# Sheet1.net
KiCad netlist of a schematic drawn in Altium Designer
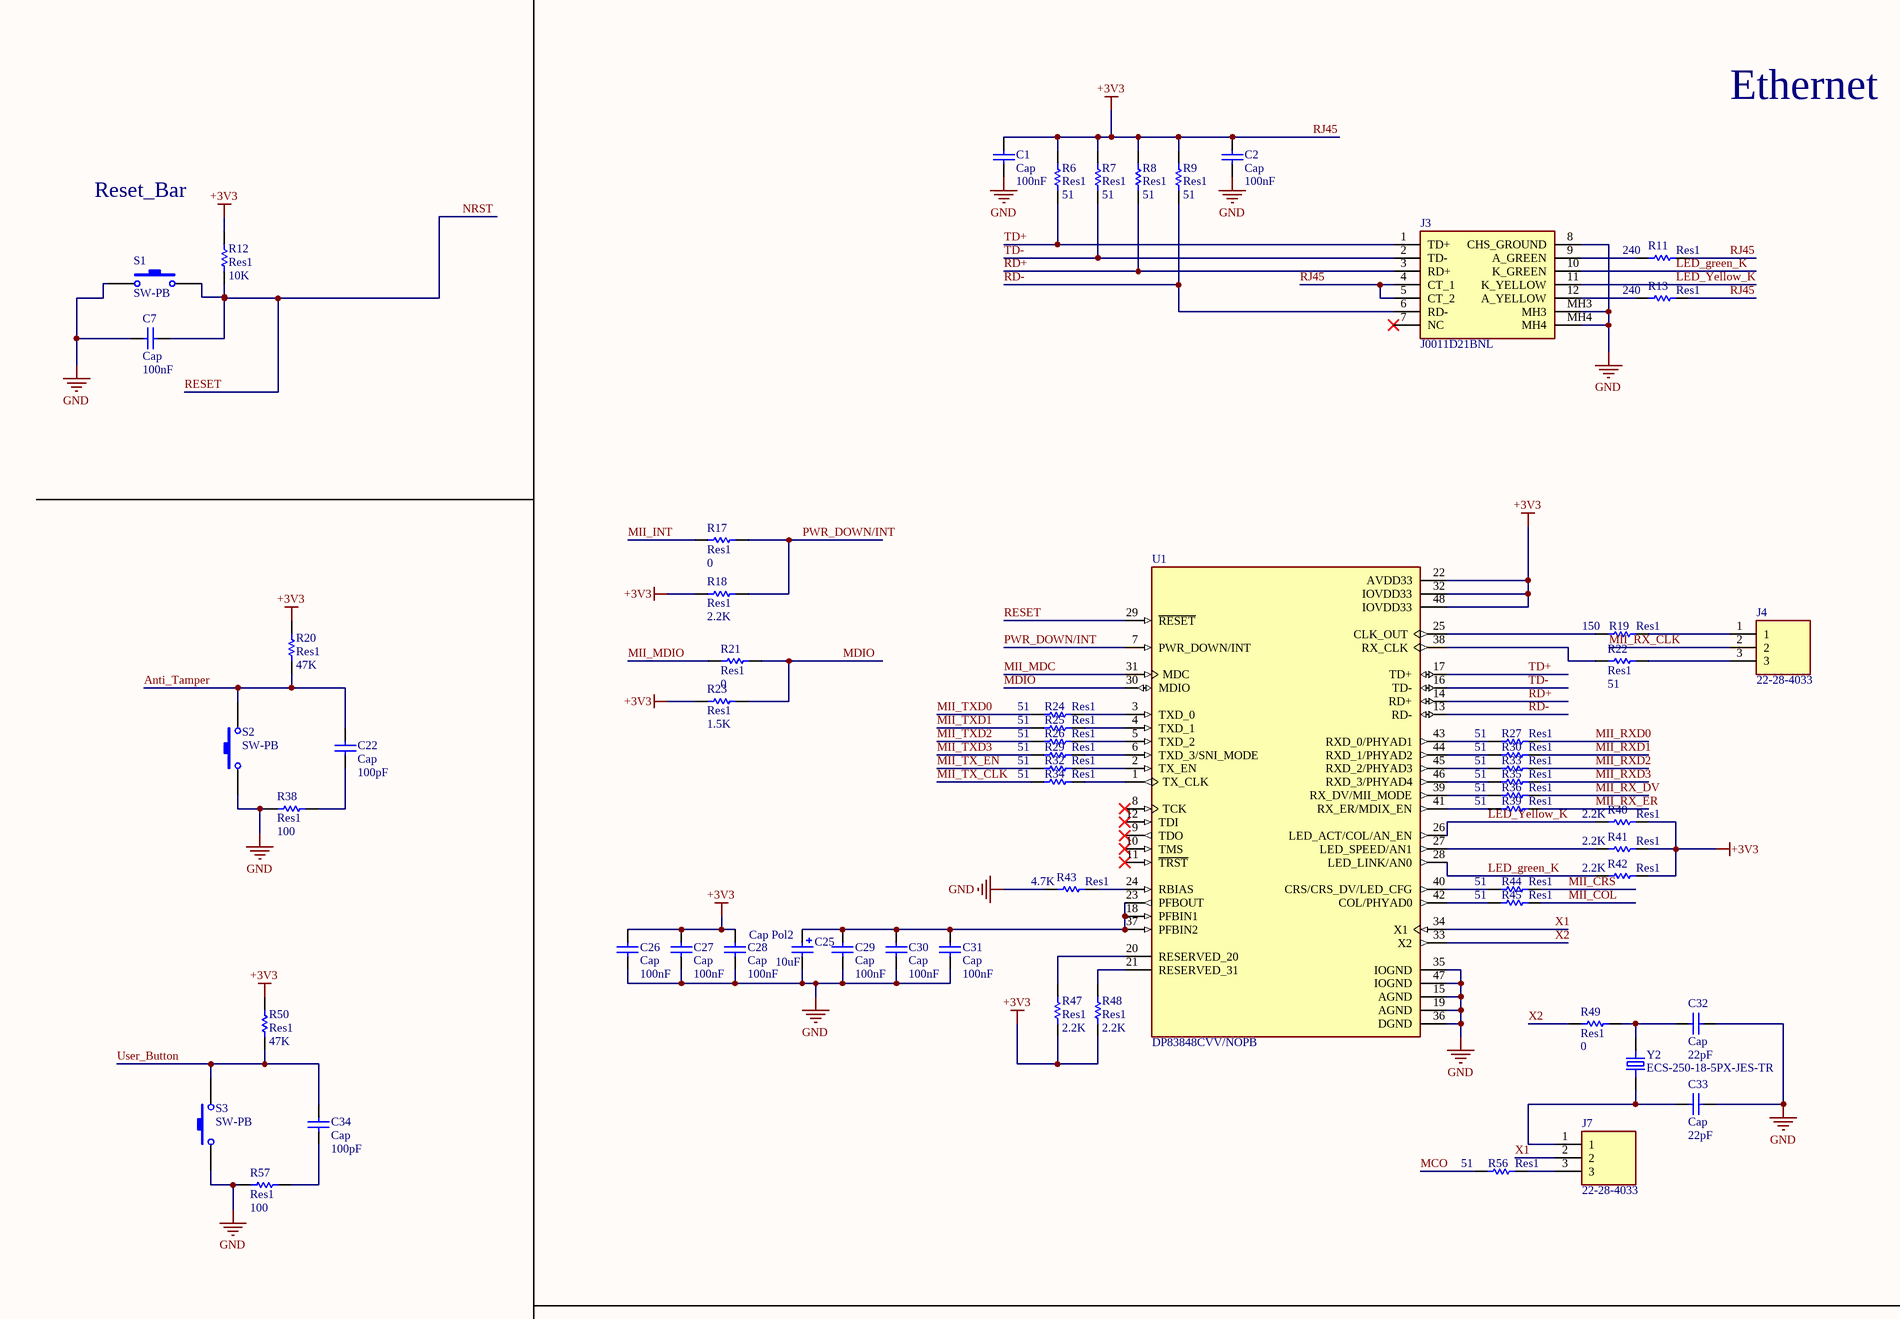
[diagram p0: Sheet1.SchDoc, top left]
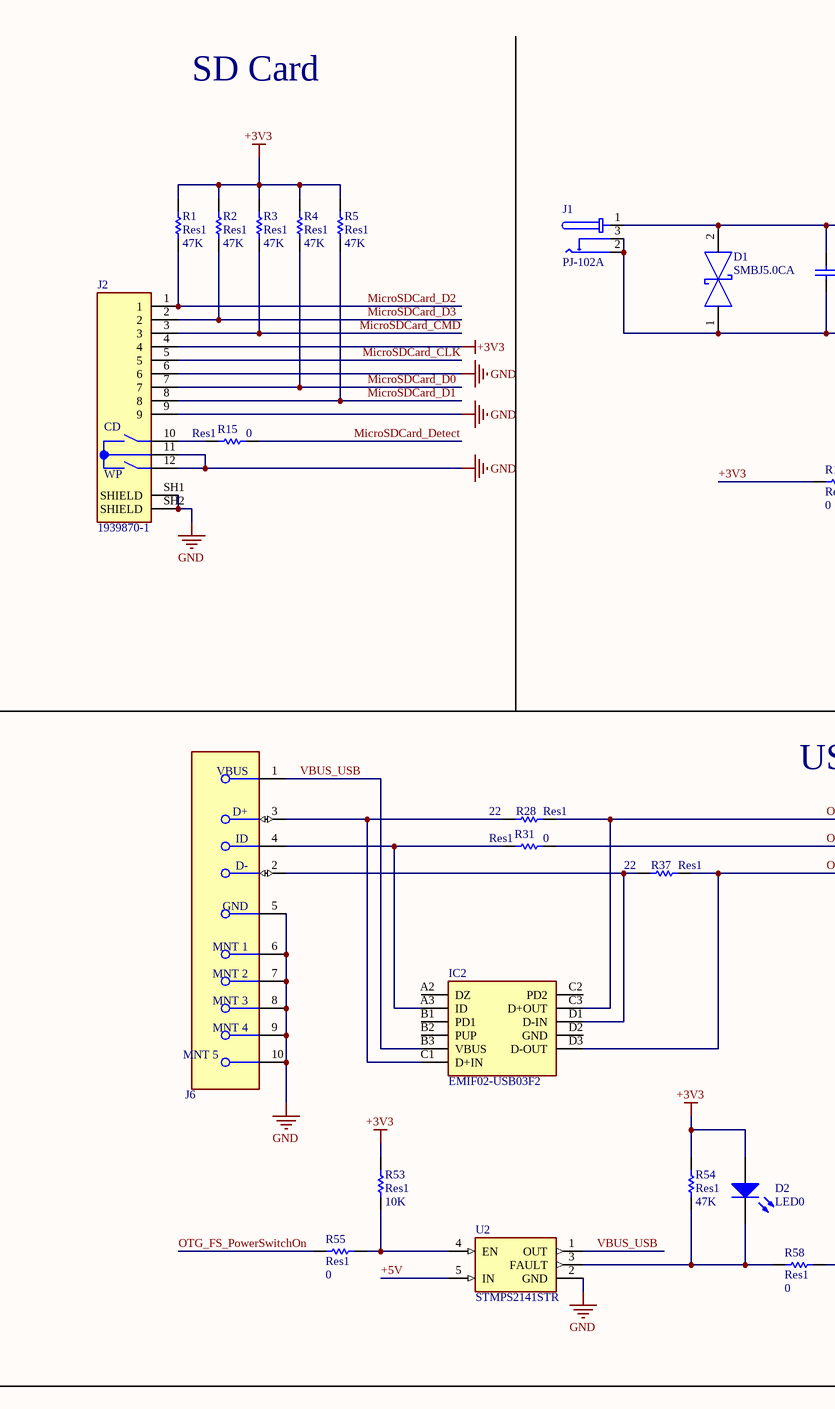
[diagram p1: Sheet1.SchDoc, top middle]
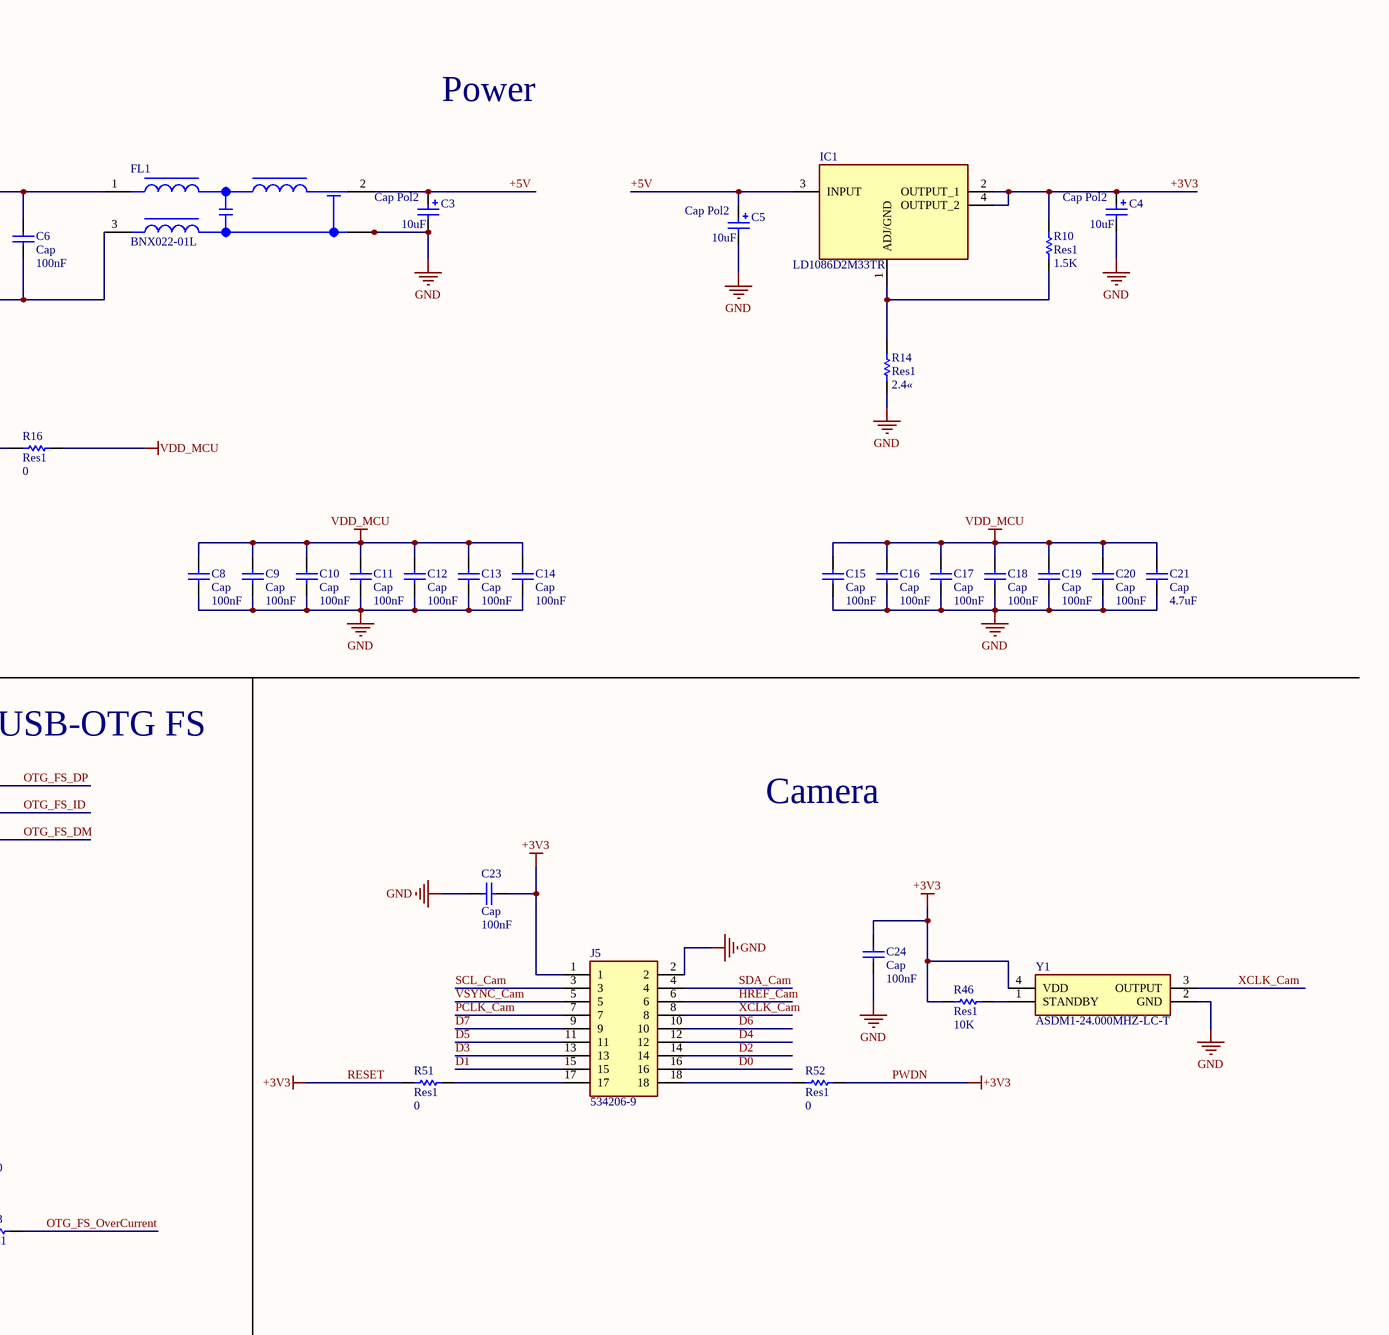
[diagram p2: Sheet1.SchDoc, top right]
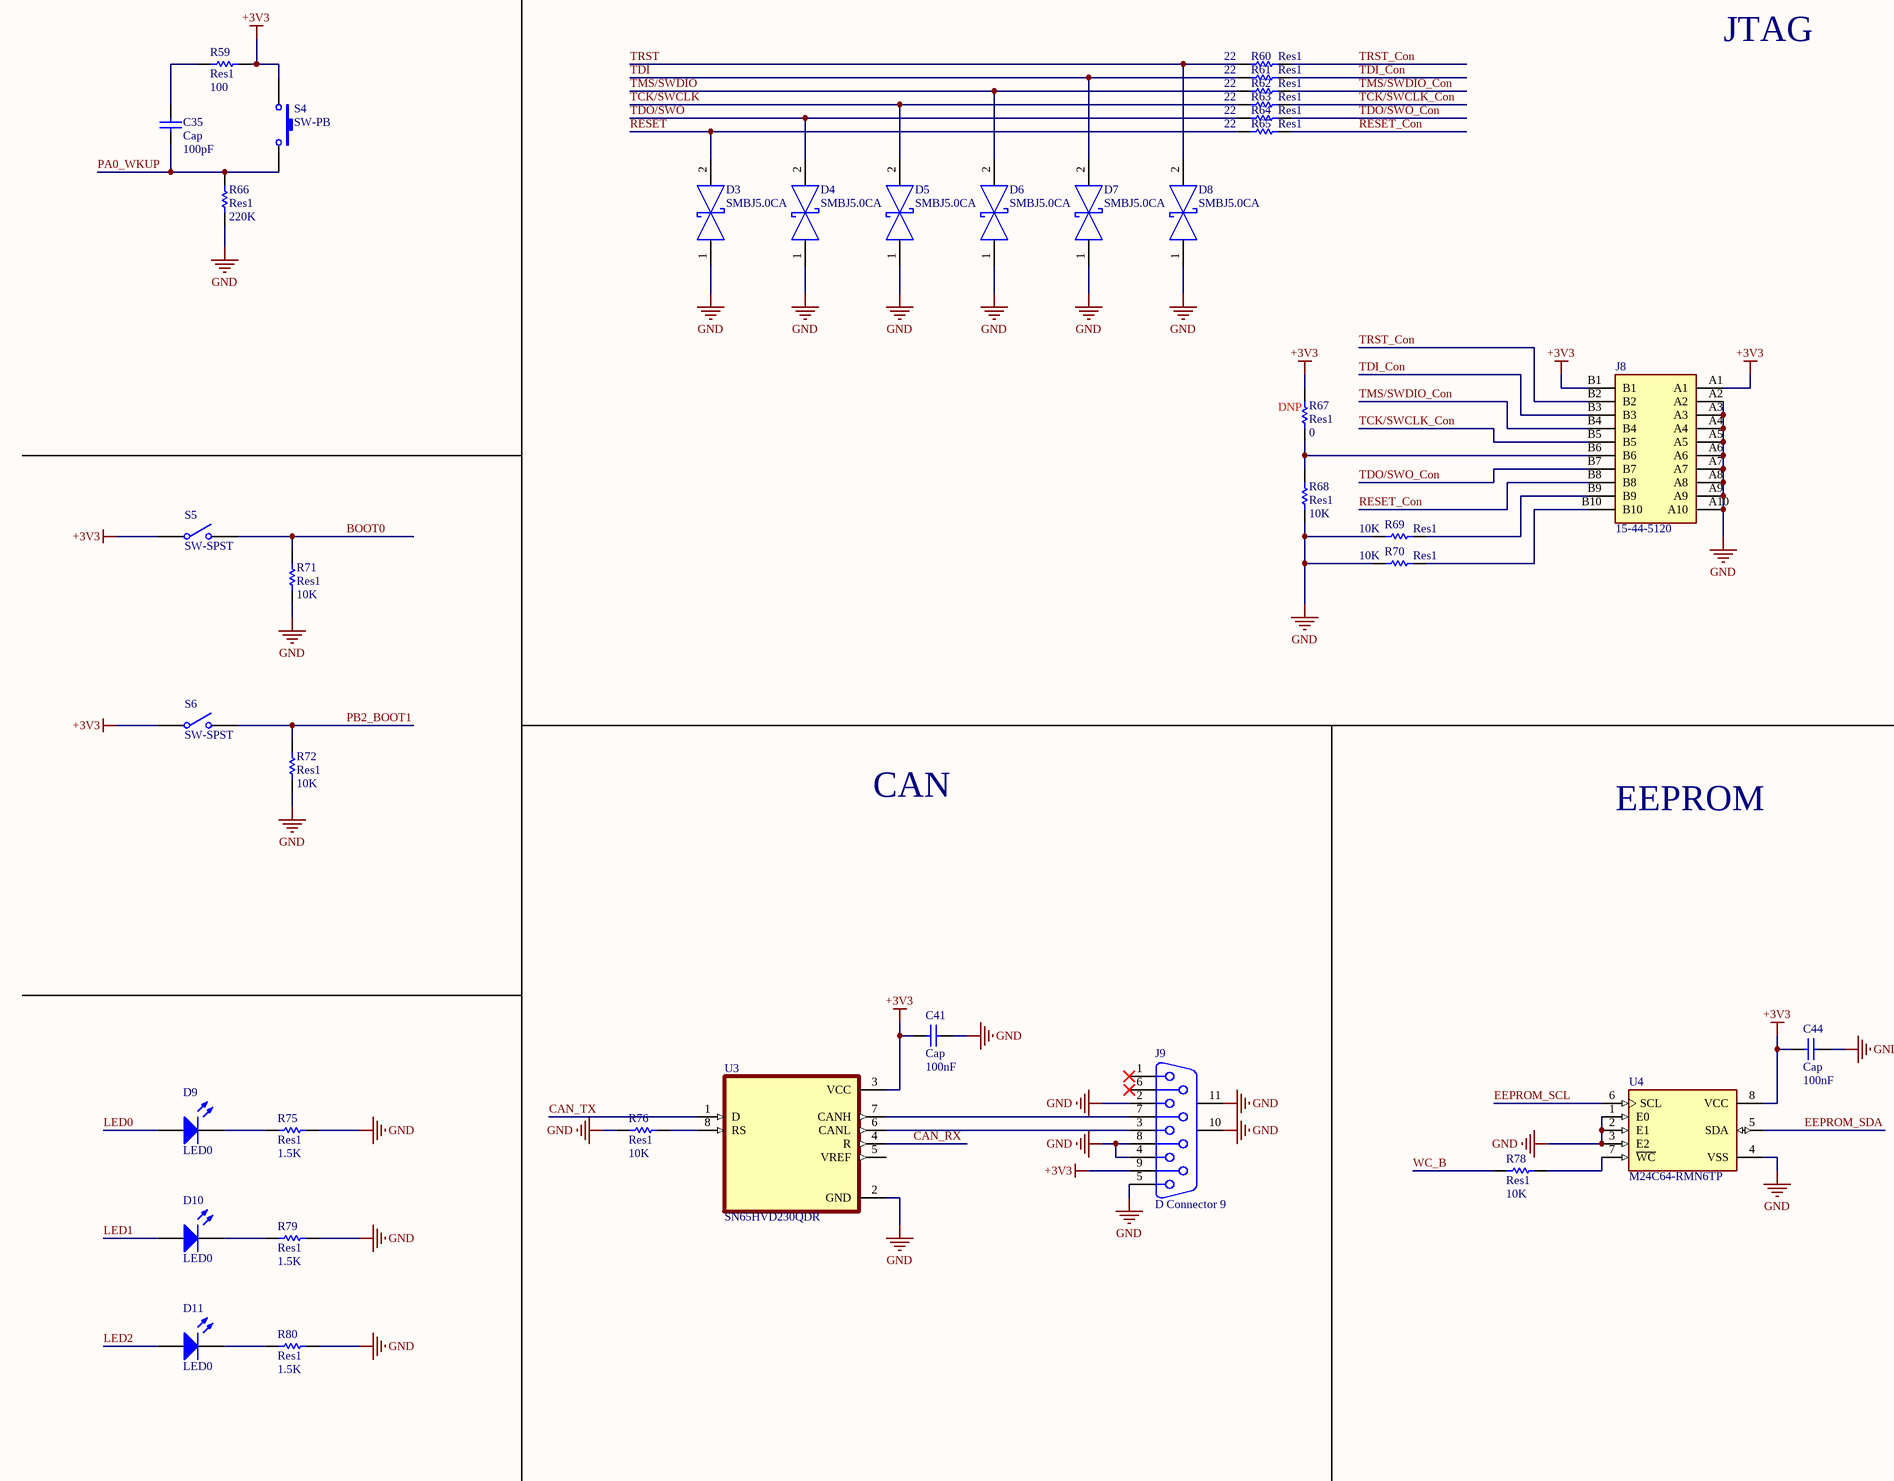
[diagram p3: Sheet1.SchDoc, bottom left]
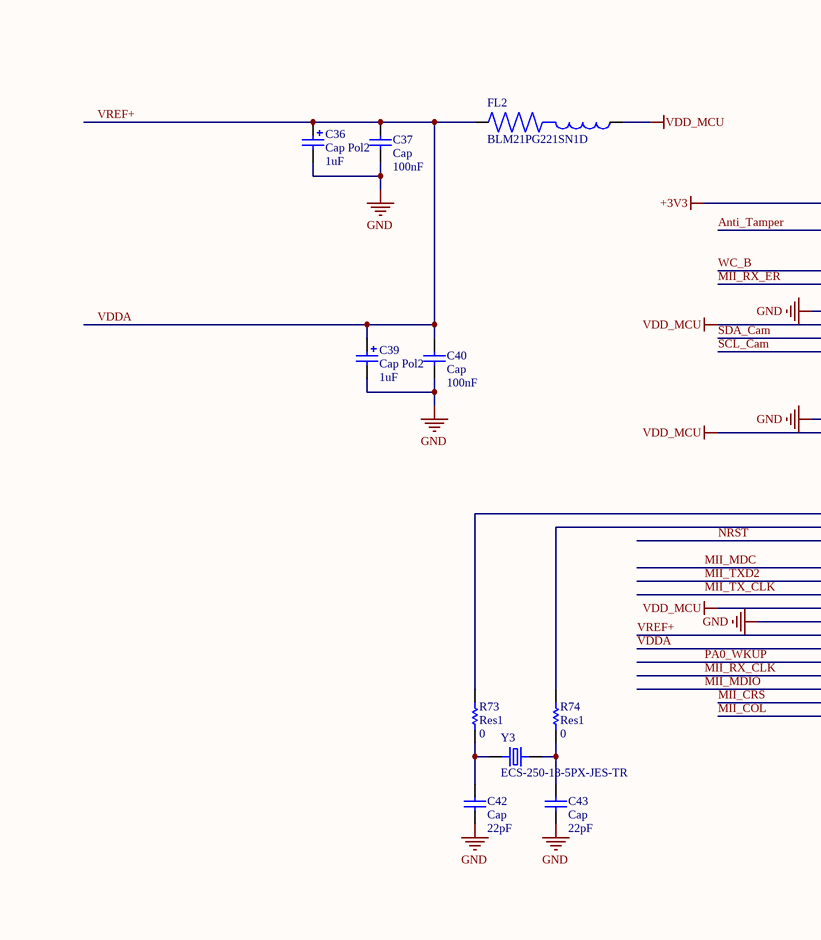
[diagram p4: Sheet1.SchDoc, bottom middle]
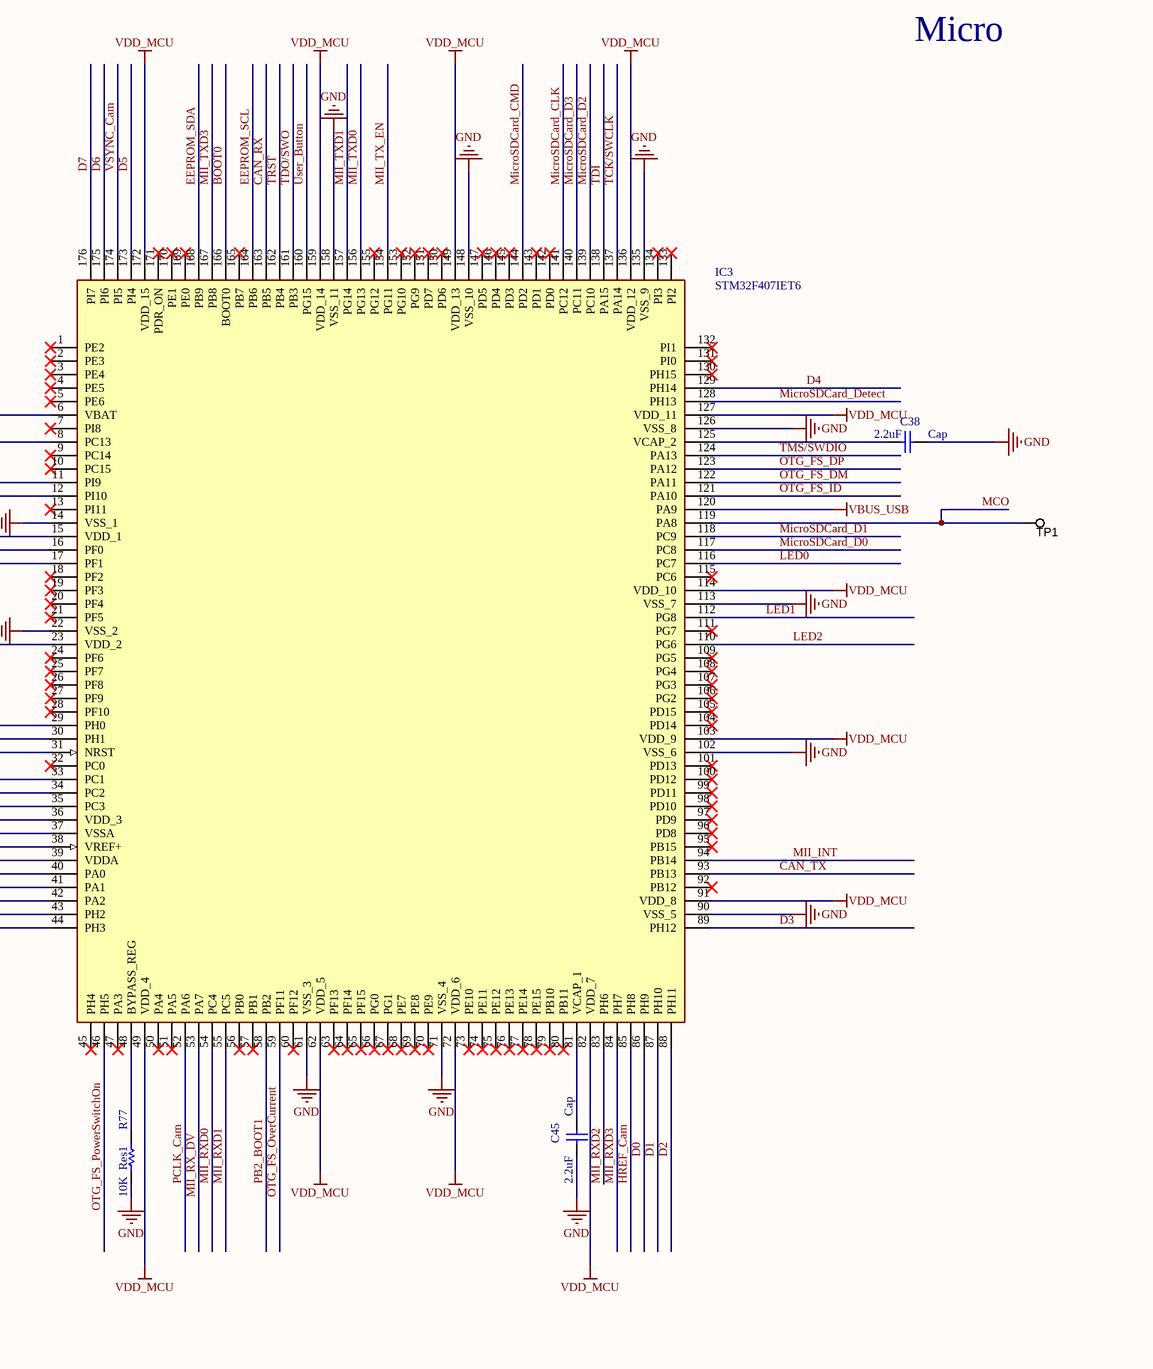
[diagram p5: Sheet1.SchDoc, bottom right]

(export (version "E")
  (design (tool "Eeschema 10.0.6"))
  (components
    (comp (ref "C1")
      (value "Cap")
      (footprint "SMD_805")
      (description "Capacitor")
      (fields (field (name "ALTIUM_VALUE") "100nF") (field (name "PUBLISHER") "Altium Limited"))
      (libsource (lib "PCB_Project") (part "Cap_1"))
    )
    (comp (ref "C2")
      (value "Cap")
      (footprint "SMD_805")
      (description "Capacitor")
      (fields (field (name "ALTIUM_VALUE") "100nF") (field (name "PUBLISHER") "Altium Limited"))
      (libsource (lib "PCB_Project") (part "Cap_1"))
    )
    (comp (ref "C3")
      (value "Cap Pol2")
      (footprint "C_B")
      (description "Polarized Capacitor (Axial)")
      (fields (field (name "ALTIUM_VALUE") "10uF") (field (name "PUBLISHER") "Altium Limited"))
      (libsource (lib "PCB_Project") (part "Cap Pol2_1"))
    )
    (comp (ref "C4")
      (value "Cap Pol2")
      (footprint "C_B")
      (description "Polarized Capacitor (Axial)")
      (fields (field (name "ALTIUM_VALUE") "10uF") (field (name "PUBLISHER") "Altium Limited"))
      (libsource (lib "PCB_Project") (part "Cap Pol2_1"))
    )
    (comp (ref "C5")
      (value "Cap Pol2")
      (footprint "C_B")
      (description "Polarized Capacitor (Axial)")
      (fields (field (name "ALTIUM_VALUE") "10uF") (field (name "PUBLISHER") "Altium Limited"))
      (libsource (lib "PCB_Project") (part "Cap Pol2_1"))
    )
    (comp (ref "C6")
      (value "Cap")
      (footprint "SMD_805")
      (description "Capacitor")
      (fields (field (name "ALTIUM_VALUE") "100nF") (field (name "PUBLISHER") "Altium Limited"))
      (libsource (lib "PCB_Project") (part "Cap_1"))
    )
    (comp (ref "C7")
      (value "Cap")
      (footprint "SMD_805")
      (description "Capacitor")
      (fields (field (name "ALTIUM_VALUE") "100nF") (field (name "PUBLISHER") "Altium Limited"))
      (libsource (lib "PCB_Project") (part "Cap_1"))
    )
    (comp (ref "C8")
      (value "Cap")
      (footprint "SMD_805")
      (description "Capacitor")
      (fields (field (name "ALTIUM_VALUE") "100nF") (field (name "PUBLISHER") "Altium Limited"))
      (libsource (lib "PCB_Project") (part "Cap_1"))
    )
    (comp (ref "C9")
      (value "Cap")
      (footprint "SMD_805")
      (description "Capacitor")
      (fields (field (name "ALTIUM_VALUE") "100nF") (field (name "PUBLISHER") "Altium Limited"))
      (libsource (lib "PCB_Project") (part "Cap_1"))
    )
    (comp (ref "C10")
      (value "Cap")
      (footprint "SMD_805")
      (description "Capacitor")
      (fields (field (name "ALTIUM_VALUE") "100nF") (field (name "PUBLISHER") "Altium Limited"))
      (libsource (lib "PCB_Project") (part "Cap_1"))
    )
    (comp (ref "C11")
      (value "Cap")
      (footprint "SMD_805")
      (description "Capacitor")
      (fields (field (name "ALTIUM_VALUE") "100nF") (field (name "PUBLISHER") "Altium Limited"))
      (libsource (lib "PCB_Project") (part "Cap_1"))
    )
    (comp (ref "C12")
      (value "Cap")
      (footprint "SMD_805")
      (description "Capacitor")
      (fields (field (name "ALTIUM_VALUE") "100nF") (field (name "PUBLISHER") "Altium Limited"))
      (libsource (lib "PCB_Project") (part "Cap_1"))
    )
    (comp (ref "C13")
      (value "Cap")
      (footprint "SMD_805")
      (description "Capacitor")
      (fields (field (name "ALTIUM_VALUE") "100nF") (field (name "PUBLISHER") "Altium Limited"))
      (libsource (lib "PCB_Project") (part "Cap_1"))
    )
    (comp (ref "C14")
      (value "Cap")
      (footprint "SMD_805")
      (description "Capacitor")
      (fields (field (name "ALTIUM_VALUE") "100nF") (field (name "PUBLISHER") "Altium Limited"))
      (libsource (lib "PCB_Project") (part "Cap_1"))
    )
    (comp (ref "C15")
      (value "Cap")
      (footprint "SMD_805")
      (description "Capacitor")
      (fields (field (name "ALTIUM_VALUE") "100nF") (field (name "PUBLISHER") "Altium Limited"))
      (libsource (lib "PCB_Project") (part "Cap_1"))
    )
    (comp (ref "C16")
      (value "Cap")
      (footprint "SMD_805")
      (description "Capacitor")
      (fields (field (name "ALTIUM_VALUE") "100nF") (field (name "PUBLISHER") "Altium Limited"))
      (libsource (lib "PCB_Project") (part "Cap_1"))
    )
    (comp (ref "C17")
      (value "Cap")
      (footprint "SMD_805")
      (description "Capacitor")
      (fields (field (name "ALTIUM_VALUE") "100nF") (field (name "PUBLISHER") "Altium Limited"))
      (libsource (lib "PCB_Project") (part "Cap_1"))
    )
    (comp (ref "C18")
      (value "Cap")
      (footprint "SMD_805")
      (description "Capacitor")
      (fields (field (name "ALTIUM_VALUE") "100nF") (field (name "PUBLISHER") "Altium Limited"))
      (libsource (lib "PCB_Project") (part "Cap_1"))
    )
    (comp (ref "C19")
      (value "Cap")
      (footprint "SMD_805")
      (description "Capacitor")
      (fields (field (name "ALTIUM_VALUE") "100nF") (field (name "PUBLISHER") "Altium Limited"))
      (libsource (lib "PCB_Project") (part "Cap_1"))
    )
    (comp (ref "C20")
      (value "Cap")
      (footprint "SMD_805")
      (description "Capacitor")
      (fields (field (name "ALTIUM_VALUE") "100nF") (field (name "PUBLISHER") "Altium Limited"))
      (libsource (lib "PCB_Project") (part "Cap_1"))
    )
    (comp (ref "C21")
      (value "Cap")
      (footprint "SMD_805")
      (description "Capacitor")
      (fields (field (name "ALTIUM_VALUE") "4.7uF") (field (name "PUBLISHER") "Altium Limited"))
      (libsource (lib "PCB_Project") (part "Cap_2"))
    )
    (comp (ref "C22")
      (value "Cap")
      (footprint "SMD_805")
      (description "Capacitor")
      (fields (field (name "ALTIUM_VALUE") "100pF") (field (name "PUBLISHER") "Altium Limited"))
      (libsource (lib "PCB_Project") (part "Cap"))
    )
    (comp (ref "C23")
      (value "Cap")
      (footprint "SMD_805")
      (description "Capacitor")
      (fields (field (name "ALTIUM_VALUE") "100nF") (field (name "PUBLISHER") "Altium Limited"))
      (libsource (lib "PCB_Project") (part "Cap_1"))
    )
    (comp (ref "C24")
      (value "Cap")
      (footprint "SMD_805")
      (description "Capacitor")
      (fields (field (name "ALTIUM_VALUE") "100nF") (field (name "PUBLISHER") "Altium Limited"))
      (libsource (lib "PCB_Project") (part "Cap_1"))
    )
    (comp (ref "C25")
      (value "Cap Pol2")
      (footprint "C_B")
      (description "Polarized Capacitor (Axial)")
      (fields (field (name "ALTIUM_VALUE") "10uF") (field (name "PUBLISHER") "Altium Limited"))
      (libsource (lib "PCB_Project") (part "Cap Pol2_1"))
    )
    (comp (ref "C26")
      (value "Cap")
      (footprint "SMD_805")
      (description "Capacitor")
      (fields (field (name "ALTIUM_VALUE") "100nF") (field (name "PUBLISHER") "Altium Limited"))
      (libsource (lib "PCB_Project") (part "Cap_1"))
    )
    (comp (ref "C27")
      (value "Cap")
      (footprint "SMD_805")
      (description "Capacitor")
      (fields (field (name "ALTIUM_VALUE") "100nF") (field (name "PUBLISHER") "Altium Limited"))
      (libsource (lib "PCB_Project") (part "Cap_1"))
    )
    (comp (ref "C28")
      (value "Cap")
      (footprint "SMD_805")
      (description "Capacitor")
      (fields (field (name "ALTIUM_VALUE") "100nF") (field (name "PUBLISHER") "Altium Limited"))
      (libsource (lib "PCB_Project") (part "Cap_1"))
    )
    (comp (ref "C29")
      (value "Cap")
      (footprint "SMD_805")
      (description "Capacitor")
      (fields (field (name "ALTIUM_VALUE") "100nF") (field (name "PUBLISHER") "Altium Limited"))
      (libsource (lib "PCB_Project") (part "Cap_1"))
    )
    (comp (ref "C30")
      (value "Cap")
      (footprint "SMD_805")
      (description "Capacitor")
      (fields (field (name "ALTIUM_VALUE") "100nF") (field (name "PUBLISHER") "Altium Limited"))
      (libsource (lib "PCB_Project") (part "Cap_1"))
    )
    (comp (ref "C31")
      (value "Cap")
      (footprint "SMD_805")
      (description "Capacitor")
      (fields (field (name "ALTIUM_VALUE") "100nF") (field (name "PUBLISHER") "Altium Limited"))
      (libsource (lib "PCB_Project") (part "Cap_1"))
    )
    (comp (ref "C32")
      (value "Cap")
      (footprint "SMD_805")
      (description "Capacitor")
      (fields (field (name "ALTIUM_VALUE") "22pF") (field (name "PUBLISHER") "Altium Limited"))
      (libsource (lib "PCB_Project") (part "Cap_3"))
    )
    (comp (ref "C33")
      (value "Cap")
      (footprint "SMD_805")
      (description "Capacitor")
      (fields (field (name "ALTIUM_VALUE") "22pF") (field (name "PUBLISHER") "Altium Limited"))
      (libsource (lib "PCB_Project") (part "Cap_3"))
    )
    (comp (ref "C34")
      (value "Cap")
      (footprint "SMD_805")
      (description "Capacitor")
      (fields (field (name "ALTIUM_VALUE") "100pF") (field (name "PUBLISHER") "Altium Limited"))
      (libsource (lib "PCB_Project") (part "Cap"))
    )
    (comp (ref "C35")
      (value "Cap")
      (footprint "SMD_805")
      (description "Capacitor")
      (fields (field (name "ALTIUM_VALUE") "100pF") (field (name "PUBLISHER") "Altium Limited"))
      (libsource (lib "PCB_Project") (part "Cap"))
    )
    (comp (ref "C36")
      (value "Cap Pol2")
      (footprint "C_B")
      (description "Polarized Capacitor (Axial)")
      (fields (field (name "ALTIUM_VALUE") "1uF") (field (name "PUBLISHER") "Altium Limited"))
      (libsource (lib "PCB_Project") (part "Cap Pol2"))
    )
    (comp (ref "C37")
      (value "Cap")
      (footprint "SMD_805")
      (description "Capacitor")
      (fields (field (name "ALTIUM_VALUE") "100nF") (field (name "PUBLISHER") "Altium Limited"))
      (libsource (lib "PCB_Project") (part "Cap_1"))
    )
    (comp (ref "C38")
      (value "Cap")
      (footprint "SMD_805")
      (description "Capacitor")
      (fields (field (name "ALTIUM_VALUE") "2.2uF") (field (name "PUBLISHER") "Altium Limited"))
      (libsource (lib "PCB_Project") (part "Cap_1"))
    )
    (comp (ref "C39")
      (value "Cap Pol2")
      (footprint "C_B")
      (description "Polarized Capacitor (Axial)")
      (fields (field (name "ALTIUM_VALUE") "1uF") (field (name "PUBLISHER") "Altium Limited"))
      (libsource (lib "PCB_Project") (part "Cap Pol2"))
    )
    (comp (ref "C40")
      (value "Cap")
      (footprint "SMD_805")
      (description "Capacitor")
      (fields (field (name "ALTIUM_VALUE") "100nF") (field (name "PUBLISHER") "Altium Limited"))
      (libsource (lib "PCB_Project") (part "Cap_1"))
    )
    (comp (ref "C41")
      (value "Cap")
      (footprint "SMD_805")
      (description "Capacitor")
      (fields (field (name "ALTIUM_VALUE") "100nF") (field (name "PUBLISHER") "Altium Limited"))
      (libsource (lib "PCB_Project") (part "Cap_1"))
    )
    (comp (ref "C42")
      (value "Cap")
      (footprint "SMD_805")
      (description "Capacitor")
      (fields (field (name "ALTIUM_VALUE") "22pF") (field (name "PUBLISHER") "Altium Limited"))
      (libsource (lib "PCB_Project") (part "Cap_3"))
    )
    (comp (ref "C43")
      (value "Cap")
      (footprint "SMD_805")
      (description "Capacitor")
      (fields (field (name "ALTIUM_VALUE") "22pF") (field (name "PUBLISHER") "Altium Limited"))
      (libsource (lib "PCB_Project") (part "Cap_3"))
    )
    (comp (ref "C44")
      (value "Cap")
      (footprint "SMD_805")
      (description "Capacitor")
      (fields (field (name "ALTIUM_VALUE") "100nF") (field (name "PUBLISHER") "Altium Limited"))
      (libsource (lib "PCB_Project") (part "Cap_1"))
    )
    (comp (ref "C45")
      (value "Cap")
      (footprint "SMD_805")
      (description "Capacitor")
      (fields (field (name "ALTIUM_VALUE") "2.2uF") (field (name "PUBLISHER") "Altium Limited"))
      (libsource (lib "PCB_Project") (part "Cap_1"))
    )
    (comp (ref "D1")
      (value "Diode_Littelfuse_SMBJ5.0CA_eec")
      (footprint "Littelfuse_SMBJ5.0CA_0")
      (description "DIODE TVS DIODE 5VWM 9.2VC DO214AA")
      (fields
        (field (name "PART NUMBER") "SMBJ5.0CA")
        (field (name "MANUFACTURER") "Littelfuse")
        (field (name "MOUSER PART NUMBER") "652-SMBJ5.0CA")
      )
      (libsource (lib "Diode_Littelfuse_SMBJ5.0CA_eec") (part "Diode_Littelfuse_SMBJ5.0CA_eec"))
    )
    (comp (ref "D2")
      (value "LED0")
      (footprint "SMD_805")
      (description "Typical INFRARED GaAs LED")
      (fields (field (name "PUBLISHER") "Altium Limited"))
      (libsource (lib "PCB_Project") (part "LED0"))
    )
    (comp (ref "D3")
      (value "Diode_Littelfuse_SMBJ5.0CA_eec")
      (footprint "Littelfuse_SMBJ5.0CA_0")
      (description "DIODE TVS DIODE 5VWM 9.2VC DO214AA")
      (fields
        (field (name "PART NUMBER") "SMBJ5.0CA")
        (field (name "MANUFACTURER") "Littelfuse")
        (field (name "MOUSER PART NUMBER") "652-SMBJ5.0CA")
      )
      (libsource (lib "Diode_Littelfuse_SMBJ5.0CA_eec") (part "Diode_Littelfuse_SMBJ5.0CA_eec"))
    )
    (comp (ref "D4")
      (value "Diode_Littelfuse_SMBJ5.0CA_eec")
      (footprint "Littelfuse_SMBJ5.0CA_0")
      (description "DIODE TVS DIODE 5VWM 9.2VC DO214AA")
      (fields
        (field (name "PART NUMBER") "SMBJ5.0CA")
        (field (name "MANUFACTURER") "Littelfuse")
        (field (name "MOUSER PART NUMBER") "652-SMBJ5.0CA")
      )
      (libsource (lib "Diode_Littelfuse_SMBJ5.0CA_eec") (part "Diode_Littelfuse_SMBJ5.0CA_eec"))
    )
    (comp (ref "D5")
      (value "Diode_Littelfuse_SMBJ5.0CA_eec")
      (footprint "Littelfuse_SMBJ5.0CA_0")
      (description "DIODE TVS DIODE 5VWM 9.2VC DO214AA")
      (fields
        (field (name "PART NUMBER") "SMBJ5.0CA")
        (field (name "MANUFACTURER") "Littelfuse")
        (field (name "MOUSER PART NUMBER") "652-SMBJ5.0CA")
      )
      (libsource (lib "Diode_Littelfuse_SMBJ5.0CA_eec") (part "Diode_Littelfuse_SMBJ5.0CA_eec"))
    )
    (comp (ref "D6")
      (value "Diode_Littelfuse_SMBJ5.0CA_eec")
      (footprint "Littelfuse_SMBJ5.0CA_0")
      (description "DIODE TVS DIODE 5VWM 9.2VC DO214AA")
      (fields
        (field (name "PART NUMBER") "SMBJ5.0CA")
        (field (name "MANUFACTURER") "Littelfuse")
        (field (name "MOUSER PART NUMBER") "652-SMBJ5.0CA")
      )
      (libsource (lib "Diode_Littelfuse_SMBJ5.0CA_eec") (part "Diode_Littelfuse_SMBJ5.0CA_eec"))
    )
    (comp (ref "D7")
      (value "Diode_Littelfuse_SMBJ5.0CA_eec")
      (footprint "Littelfuse_SMBJ5.0CA_0")
      (description "DIODE TVS DIODE 5VWM 9.2VC DO214AA")
      (fields
        (field (name "PART NUMBER") "SMBJ5.0CA")
        (field (name "MANUFACTURER") "Littelfuse")
        (field (name "MOUSER PART NUMBER") "652-SMBJ5.0CA")
      )
      (libsource (lib "Diode_Littelfuse_SMBJ5.0CA_eec") (part "Diode_Littelfuse_SMBJ5.0CA_eec"))
    )
    (comp (ref "D8")
      (value "Diode_Littelfuse_SMBJ5.0CA_eec")
      (footprint "Littelfuse_SMBJ5.0CA_0")
      (description "DIODE TVS DIODE 5VWM 9.2VC DO214AA")
      (fields
        (field (name "PART NUMBER") "SMBJ5.0CA")
        (field (name "MANUFACTURER") "Littelfuse")
        (field (name "MOUSER PART NUMBER") "652-SMBJ5.0CA")
      )
      (libsource (lib "Diode_Littelfuse_SMBJ5.0CA_eec") (part "Diode_Littelfuse_SMBJ5.0CA_eec"))
    )
    (comp (ref "D9")
      (value "LED0")
      (footprint "SMD_805")
      (description "Typical INFRARED GaAs LED")
      (fields (field (name "PUBLISHER") "Altium Limited"))
      (libsource (lib "PCB_Project") (part "LED0"))
    )
    (comp (ref "D10")
      (value "LED0")
      (footprint "SMD_805")
      (description "Typical INFRARED GaAs LED")
      (fields (field (name "PUBLISHER") "Altium Limited"))
      (libsource (lib "PCB_Project") (part "LED0"))
    )
    (comp (ref "D11")
      (value "LED0")
      (footprint "SMD_805")
      (description "Typical INFRARED GaAs LED")
      (fields (field (name "PUBLISHER") "Altium Limited"))
      (libsource (lib "PCB_Project") (part "LED0"))
    )
    (comp (ref "FL1")
      (value "BNX022-01L")
      (footprint "FIL_BNX022-01L")
      (description "LC EMI Filter 5th Order Low Pass 2 Channel C = 1ÂµF 20A 4-SMD, No Lead")
      (fields (field (name "MF") "Murata"))
      (libsource (lib "BNX022-01L") (part "BNX022-01L"))
    )
    (comp (ref "FL2")
      (value "BLM21PG221SN1D")
      (footprint "BEADC2012X105N")
      (libsource (lib "BLM21PG221SN1D") (part "BLM21PG221SN1D"))
    )
    (comp (ref "IC1")
      (value "LD1086D2M33TR")
      (footprint "SamacSys:LD1086D2M33TR")
      (description "Integrated Circuit")
      (fields (field (name "MOUSER PART NUMBER") "511-LD1086D2M33-TR"))
      (libsource (lib "SamacSys") (part "LD1086D2M33TR"))
    )
    (comp (ref "IC2")
      (value "EMIF02-USB03F2")
      (footprint "SamacSys:BGA11C50P3X4_144X194X72")
      (description "Integrated Circuit")
      (fields (field (name "MOUSER PART NUMBER") "511-EMIF02-USB03F2"))
      (libsource (lib "*") (part "EMIF02-USB03F2"))
    )
    (comp (ref "IC3")
      (value "STM32F407IET6")
      (footprint "SamacSys:QFP50P2600X2600X160-176N")
      (description "Integrated Circuit")
      (fields (field (name "MOUSER PART NUMBER") "511-STM32F407IET6"))
      (libsource (lib "*") (part "STM32F407IET6"))
    )
    (comp (ref "J1")
      (value "PJ-102A")
      (footprint "CUI_PJ-102A")
      (description "2.0 x 6.5 mm, 2.5 A, Horizontal, Through Hole, Tapered Pins, Dc Power Jack Connector")
      (fields (field (name "MF") "Same Sky"))
      (libsource (lib "PJ-102A") (part "PJ-102A"))
    )
    (comp (ref "J2")
      (value "1939870-1")
      (footprint "TE_1939870-1")
      (libsource (lib "1939870-1") (part "1939870-1"))
    )
    (comp (ref "J3")
      (value "J0011D21BNL")
      (footprint "SamacSys:J0011D21BNL")
      (description "Connector")
      (fields (field (name "MOUSER PART NUMBER") "673-J0011D21BNL"))
      (libsource (lib "SamacSys") (part "J0011D21BNL"))
    )
    (comp (ref "J4")
      (value "22-28-4033")
      (footprint "HDRV3W66P0X254_1X3_762X249X838P")
      (description "MOLEX - 22-28-4033 - CONNECTOR, HEADER, 3POS, 1ROW, 2.54MM")
      (fields (field (name "MOUSER PART NUMBER") "538-22-28-4033"))
      (libsource (lib "22-28-4033") (part "22-28-4033"))
    )
    (comp (ref "J5")
      (value "534206-9")
      (footprint "SamacSys:5342069")
      (description "Connector")
      (fields (field (name "MOUSER PART NUMBER") "571-5342069"))
      (libsource (lib "*") (part "534206-9"))
    )
    (comp (ref "J6")
      (value "47590-0001")
      (footprint "Molex_0_MFG")
      (libsource (lib "Conn_Molex_47590-0001_eec") (part "47590-0001"))
    )
    (comp (ref "J7")
      (value "22-28-4033")
      (footprint "HDRV3W66P0X254_1X3_762X249X838P")
      (description "MOLEX - 22-28-4033 - CONNECTOR, HEADER, 3POS, 1ROW, 2.54MM")
      (fields (field (name "MOUSER PART NUMBER") "538-22-28-4033"))
      (libsource (lib "22-28-4033") (part "22-28-4033"))
    )
    (comp (ref "J8")
      (value "15-44-5120")
      (footprint "SamacSys:15445120")
      (description "Connector")
      (fields (field (name "MOUSER PART NUMBER") "538-15-44-5120"))
      (libsource (lib "SamacSys") (part "15-44-5120"))
    )
    (comp (ref "J9")
      (value "D Connector 9")
      (footprint "COM_3d")
      (description "Receptacle Assembly, 9 Position, Right Angle")
      (fields (field (name "PUBLISHER") "Altium Limited"))
      (libsource (lib "PCB_Project") (part "D Connector 9"))
    )
    (comp (ref "R1")
      (value "Res1")
      (footprint "SMD_805")
      (description "Resistor")
      (fields (field (name "ALTIUM_VALUE") "47K") (field (name "PUBLISHER") "Altium Limited"))
      (libsource (lib "PCB_Project") (part "Res1_4"))
    )
    (comp (ref "R2")
      (value "Res1")
      (footprint "SMD_805")
      (description "Resistor")
      (fields (field (name "ALTIUM_VALUE") "47K") (field (name "PUBLISHER") "Altium Limited"))
      (libsource (lib "PCB_Project") (part "Res1_4"))
    )
    (comp (ref "R3")
      (value "Res1")
      (footprint "SMD_805")
      (description "Resistor")
      (fields (field (name "ALTIUM_VALUE") "47K") (field (name "PUBLISHER") "Altium Limited"))
      (libsource (lib "PCB_Project") (part "Res1_4"))
    )
    (comp (ref "R4")
      (value "Res1")
      (footprint "SMD_805")
      (description "Resistor")
      (fields (field (name "ALTIUM_VALUE") "47K") (field (name "PUBLISHER") "Altium Limited"))
      (libsource (lib "PCB_Project") (part "Res1_4"))
    )
    (comp (ref "R5")
      (value "Res1")
      (footprint "SMD_805")
      (description "Resistor")
      (fields (field (name "ALTIUM_VALUE") "47K") (field (name "PUBLISHER") "Altium Limited"))
      (libsource (lib "PCB_Project") (part "Res1_4"))
    )
    (comp (ref "R6")
      (value "Res1")
      (footprint "SMD_805")
      (description "Resistor")
      (fields (field (name "ALTIUM_VALUE") "51") (field (name "PUBLISHER") "Altium Limited"))
      (libsource (lib "PCB_Project") (part "Res1_4"))
    )
    (comp (ref "R7")
      (value "Res1")
      (footprint "SMD_805")
      (description "Resistor")
      (fields (field (name "ALTIUM_VALUE") "51") (field (name "PUBLISHER") "Altium Limited"))
      (libsource (lib "PCB_Project") (part "Res1_4"))
    )
    (comp (ref "R8")
      (value "Res1")
      (footprint "SMD_805")
      (description "Resistor")
      (fields (field (name "ALTIUM_VALUE") "51") (field (name "PUBLISHER") "Altium Limited"))
      (libsource (lib "PCB_Project") (part "Res1_4"))
    )
    (comp (ref "R9")
      (value "Res1")
      (footprint "SMD_805")
      (description "Resistor")
      (fields (field (name "ALTIUM_VALUE") "51") (field (name "PUBLISHER") "Altium Limited"))
      (libsource (lib "PCB_Project") (part "Res1_4"))
    )
    (comp (ref "R10")
      (value "Res1")
      (footprint "SMD_805")
      (description "Resistor")
      (fields (field (name "ALTIUM_VALUE") "1.5K") (field (name "PUBLISHER") "Altium Limited"))
      (libsource (lib "PCB_Project") (part "Res1_8"))
    )
    (comp (ref "R11")
      (value "Res1")
      (footprint "SMD_805")
      (description "Resistor")
      (fields (field (name "ALTIUM_VALUE") "240") (field (name "PUBLISHER") "Altium Limited"))
      (libsource (lib "PCB_Project") (part "Res1_4"))
    )
    (comp (ref "R12")
      (value "Res1")
      (footprint "SMD_805")
      (description "Resistor")
      (fields (field (name "ALTIUM_VALUE") "10K") (field (name "PUBLISHER") "Altium Limited"))
      (libsource (lib "PCB_Project") (part "Res1_6"))
    )
    (comp (ref "R13")
      (value "Res1")
      (footprint "SMD_805")
      (description "Resistor")
      (fields (field (name "ALTIUM_VALUE") "240") (field (name "PUBLISHER") "Altium Limited"))
      (libsource (lib "PCB_Project") (part "Res1_4"))
    )
    (comp (ref "R14")
      (value "Res1")
      (footprint "SMD_805")
      (description "Resistor")
      (fields (field (name "ALTIUM_VALUE") "2.4«") (field (name "PUBLISHER") "Altium Limited"))
      (libsource (lib "PCB_Project") (part "Res1_8"))
    )
    (comp (ref "R15")
      (value "Res1")
      (footprint "SMD_805")
      (description "Resistor")
      (fields (field (name "ALTIUM_VALUE") "0") (field (name "PUBLISHER") "Altium Limited"))
      (libsource (lib "PCB_Project") (part "Res1_4"))
    )
    (comp (ref "R16")
      (value "Res1")
      (footprint "SMD_805")
      (description "Resistor")
      (fields (field (name "ALTIUM_VALUE") "0") (field (name "PUBLISHER") "Altium Limited"))
      (libsource (lib "PCB_Project") (part "Res1_4"))
    )
    (comp (ref "R17")
      (value "Res1")
      (footprint "SMD_805")
      (description "Resistor")
      (fields (field (name "ALTIUM_VALUE") "0") (field (name "PUBLISHER") "Altium Limited"))
      (libsource (lib "PCB_Project") (part "Res1_4"))
    )
    (comp (ref "R18")
      (value "Res1")
      (footprint "SMD_805")
      (description "Resistor")
      (fields (field (name "ALTIUM_VALUE") "2.2K") (field (name "PUBLISHER") "Altium Limited"))
      (libsource (lib "PCB_Project") (part "Res1_4"))
    )
    (comp (ref "R19")
      (value "Res1")
      (footprint "SMD_805")
      (description "Resistor")
      (fields (field (name "ALTIUM_VALUE") "150") (field (name "PUBLISHER") "Altium Limited"))
      (libsource (lib "PCB_Project") (part "Res1_4"))
    )
    (comp (ref "R20")
      (value "Res1")
      (footprint "SMD_805")
      (description "Resistor")
      (fields (field (name "ALTIUM_VALUE") "47K") (field (name "PUBLISHER") "Altium Limited"))
      (libsource (lib "PCB_Project") (part "Res1_4"))
    )
    (comp (ref "R21")
      (value "Res1")
      (footprint "SMD_805")
      (description "Resistor")
      (fields (field (name "ALTIUM_VALUE") "0") (field (name "PUBLISHER") "Altium Limited"))
      (libsource (lib "PCB_Project") (part "Res1_4"))
    )
    (comp (ref "R22")
      (value "Res1")
      (footprint "SMD_805")
      (description "Resistor")
      (fields (field (name "ALTIUM_VALUE") "51") (field (name "PUBLISHER") "Altium Limited"))
      (libsource (lib "PCB_Project") (part "Res1_4"))
    )
    (comp (ref "R23")
      (value "Res1")
      (footprint "SMD_805")
      (description "Resistor")
      (fields (field (name "ALTIUM_VALUE") "1.5K") (field (name "PUBLISHER") "Altium Limited"))
      (libsource (lib "PCB_Project") (part "Res1_4"))
    )
    (comp (ref "R24")
      (value "Res1")
      (footprint "SMD_805")
      (description "Resistor")
      (fields (field (name "ALTIUM_VALUE") "51") (field (name "PUBLISHER") "Altium Limited"))
      (libsource (lib "PCB_Project") (part "Res1_4"))
    )
    (comp (ref "R25")
      (value "Res1")
      (footprint "SMD_805")
      (description "Resistor")
      (fields (field (name "ALTIUM_VALUE") "51") (field (name "PUBLISHER") "Altium Limited"))
      (libsource (lib "PCB_Project") (part "Res1_4"))
    )
    (comp (ref "R26")
      (value "Res1")
      (footprint "SMD_805")
      (description "Resistor")
      (fields (field (name "ALTIUM_VALUE") "51") (field (name "PUBLISHER") "Altium Limited"))
      (libsource (lib "PCB_Project") (part "Res1_4"))
    )
    (comp (ref "R27")
      (value "Res1")
      (footprint "SMD_805")
      (description "Resistor")
      (fields (field (name "ALTIUM_VALUE") "51") (field (name "PUBLISHER") "Altium Limited"))
      (libsource (lib "PCB_Project") (part "Res1_4"))
    )
    (comp (ref "R28")
      (value "Res1")
      (footprint "SMD_805")
      (description "Resistor")
      (fields (field (name "ALTIUM_VALUE") "22") (field (name "PUBLISHER") "Altium Limited"))
      (libsource (lib "PCB_Project") (part "Res1_4"))
    )
    (comp (ref "R29")
      (value "Res1")
      (footprint "SMD_805")
      (description "Resistor")
      (fields (field (name "ALTIUM_VALUE") "51") (field (name "PUBLISHER") "Altium Limited"))
      (libsource (lib "PCB_Project") (part "Res1_4"))
    )
    (comp (ref "R30")
      (value "Res1")
      (footprint "SMD_805")
      (description "Resistor")
      (fields (field (name "ALTIUM_VALUE") "51") (field (name "PUBLISHER") "Altium Limited"))
      (libsource (lib "PCB_Project") (part "Res1_4"))
    )
    (comp (ref "R31")
      (value "Res1")
      (footprint "SMD_805")
      (description "Resistor")
      (fields (field (name "ALTIUM_VALUE") "0") (field (name "PUBLISHER") "Altium Limited"))
      (libsource (lib "PCB_Project") (part "Res1_4"))
    )
    (comp (ref "R32")
      (value "Res1")
      (footprint "SMD_805")
      (description "Resistor")
      (fields (field (name "ALTIUM_VALUE") "51") (field (name "PUBLISHER") "Altium Limited"))
      (libsource (lib "PCB_Project") (part "Res1_4"))
    )
    (comp (ref "R33")
      (value "Res1")
      (footprint "SMD_805")
      (description "Resistor")
      (fields (field (name "ALTIUM_VALUE") "51") (field (name "PUBLISHER") "Altium Limited"))
      (libsource (lib "PCB_Project") (part "Res1_4"))
    )
    (comp (ref "R34")
      (value "Res1")
      (footprint "SMD_805")
      (description "Resistor")
      (fields (field (name "ALTIUM_VALUE") "51") (field (name "PUBLISHER") "Altium Limited"))
      (libsource (lib "PCB_Project") (part "Res1_4"))
    )
    (comp (ref "R35")
      (value "Res1")
      (footprint "SMD_805")
      (description "Resistor")
      (fields (field (name "ALTIUM_VALUE") "51") (field (name "PUBLISHER") "Altium Limited"))
      (libsource (lib "PCB_Project") (part "Res1_4"))
    )
    (comp (ref "R36")
      (value "Res1")
      (footprint "SMD_805")
      (description "Resistor")
      (fields (field (name "ALTIUM_VALUE") "51") (field (name "PUBLISHER") "Altium Limited"))
      (libsource (lib "PCB_Project") (part "Res1_4"))
    )
    (comp (ref "R37")
      (value "Res1")
      (footprint "SMD_805")
      (description "Resistor")
      (fields (field (name "ALTIUM_VALUE") "22") (field (name "PUBLISHER") "Altium Limited"))
      (libsource (lib "PCB_Project") (part "Res1_4"))
    )
    (comp (ref "R38")
      (value "Res1")
      (footprint "SMD_805")
      (description "Resistor")
      (fields (field (name "ALTIUM_VALUE") "100") (field (name "PUBLISHER") "Altium Limited"))
      (libsource (lib "PCB_Project") (part "Res1_4"))
    )
    (comp (ref "R39")
      (value "Res1")
      (footprint "SMD_805")
      (description "Resistor")
      (fields (field (name "ALTIUM_VALUE") "51") (field (name "PUBLISHER") "Altium Limited"))
      (libsource (lib "PCB_Project") (part "Res1_4"))
    )
    (comp (ref "R40")
      (value "Res1")
      (footprint "SMD_805")
      (description "Resistor")
      (fields (field (name "ALTIUM_VALUE") "2.2K") (field (name "PUBLISHER") "Altium Limited"))
      (libsource (lib "PCB_Project") (part "Res1_4"))
    )
    (comp (ref "R41")
      (value "Res1")
      (footprint "SMD_805")
      (description "Resistor")
      (fields (field (name "ALTIUM_VALUE") "2.2K") (field (name "PUBLISHER") "Altium Limited"))
      (libsource (lib "PCB_Project") (part "Res1_4"))
    )
    (comp (ref "R42")
      (value "Res1")
      (footprint "SMD_805")
      (description "Resistor")
      (fields (field (name "ALTIUM_VALUE") "2.2K") (field (name "PUBLISHER") "Altium Limited"))
      (libsource (lib "PCB_Project") (part "Res1_4"))
    )
    (comp (ref "R43")
      (value "Res1")
      (footprint "SMD_805")
      (description "Resistor")
      (fields (field (name "ALTIUM_VALUE") "4.7K") (field (name "PUBLISHER") "Altium Limited"))
      (libsource (lib "PCB_Project") (part "Res1_5"))
    )
    (comp (ref "R44")
      (value "Res1")
      (footprint "SMD_805")
      (description "Resistor")
      (fields (field (name "ALTIUM_VALUE") "51") (field (name "PUBLISHER") "Altium Limited"))
      (libsource (lib "PCB_Project") (part "Res1_4"))
    )
    (comp (ref "R45")
      (value "Res1")
      (footprint "SMD_805")
      (description "Resistor")
      (fields (field (name "ALTIUM_VALUE") "51") (field (name "PUBLISHER") "Altium Limited"))
      (libsource (lib "PCB_Project") (part "Res1_4"))
    )
    (comp (ref "R46")
      (value "Res1")
      (footprint "SMD_805")
      (description "Resistor")
      (fields (field (name "ALTIUM_VALUE") "10K") (field (name "PUBLISHER") "Altium Limited"))
      (libsource (lib "PCB_Project") (part "Res1_6"))
    )
    (comp (ref "R47")
      (value "Res1")
      (footprint "SMD_805")
      (description "Resistor")
      (fields (field (name "ALTIUM_VALUE") "2.2K") (field (name "PUBLISHER") "Altium Limited"))
      (libsource (lib "PCB_Project") (part "Res1_4"))
    )
    (comp (ref "R48")
      (value "Res1")
      (footprint "SMD_805")
      (description "Resistor")
      (fields (field (name "ALTIUM_VALUE") "2.2K") (field (name "PUBLISHER") "Altium Limited"))
      (libsource (lib "PCB_Project") (part "Res1_4"))
    )
    (comp (ref "R49")
      (value "Res1")
      (footprint "SMD_805")
      (description "Resistor")
      (fields (field (name "ALTIUM_VALUE") "0") (field (name "PUBLISHER") "Altium Limited"))
      (libsource (lib "PCB_Project") (part "Res1_4"))
    )
    (comp (ref "R50")
      (value "Res1")
      (footprint "SMD_805")
      (description "Resistor")
      (fields (field (name "ALTIUM_VALUE") "47K") (field (name "PUBLISHER") "Altium Limited"))
      (libsource (lib "PCB_Project") (part "Res1_4"))
    )
    (comp (ref "R51")
      (value "Res1")
      (footprint "SMD_805")
      (description "Resistor")
      (fields (field (name "ALTIUM_VALUE") "0") (field (name "PUBLISHER") "Altium Limited"))
      (libsource (lib "PCB_Project") (part "Res1_4"))
    )
    (comp (ref "R52")
      (value "Res1")
      (footprint "SMD_805")
      (description "Resistor")
      (fields (field (name "ALTIUM_VALUE") "0") (field (name "PUBLISHER") "Altium Limited"))
      (libsource (lib "PCB_Project") (part "Res1_4"))
    )
    (comp (ref "R53")
      (value "Res1")
      (footprint "SMD_805")
      (description "Resistor")
      (fields (field (name "ALTIUM_VALUE") "10K") (field (name "PUBLISHER") "Altium Limited"))
      (libsource (lib "PCB_Project") (part "Res1_6"))
    )
    (comp (ref "R54")
      (value "Res1")
      (footprint "SMD_805")
      (description "Resistor")
      (fields (field (name "ALTIUM_VALUE") "47K") (field (name "PUBLISHER") "Altium Limited"))
      (libsource (lib "PCB_Project") (part "Res1_6"))
    )
    (comp (ref "R55")
      (value "Res1")
      (footprint "SMD_805")
      (description "Resistor")
      (fields (field (name "ALTIUM_VALUE") "0") (field (name "PUBLISHER") "Altium Limited"))
      (libsource (lib "PCB_Project") (part "Res1_4"))
    )
    (comp (ref "R56")
      (value "Res1")
      (footprint "SMD_805")
      (description "Resistor")
      (fields (field (name "ALTIUM_VALUE") "51") (field (name "PUBLISHER") "Altium Limited"))
      (libsource (lib "PCB_Project") (part "Res1_4"))
    )
    (comp (ref "R57")
      (value "Res1")
      (footprint "SMD_805")
      (description "Resistor")
      (fields (field (name "ALTIUM_VALUE") "100") (field (name "PUBLISHER") "Altium Limited"))
      (libsource (lib "PCB_Project") (part "Res1_4"))
    )
    (comp (ref "R58")
      (value "Res1")
      (footprint "SMD_805")
      (description "Resistor")
      (fields (field (name "ALTIUM_VALUE") "0") (field (name "PUBLISHER") "Altium Limited"))
      (libsource (lib "PCB_Project") (part "Res1_4"))
    )
    (comp (ref "R59")
      (value "Res1")
      (footprint "SMD_805")
      (description "Resistor")
      (fields (field (name "ALTIUM_VALUE") "100") (field (name "PUBLISHER") "Altium Limited"))
      (libsource (lib "PCB_Project") (part "Res1_4"))
    )
    (comp (ref "R60")
      (value "Res1")
      (footprint "SMD_805")
      (description "Resistor")
      (fields (field (name "ALTIUM_VALUE") "22") (field (name "PUBLISHER") "Altium Limited"))
      (libsource (lib "PCB_Project") (part "Res1_4"))
    )
    (comp (ref "R61")
      (value "Res1")
      (footprint "SMD_805")
      (description "Resistor")
      (fields (field (name "ALTIUM_VALUE") "22") (field (name "PUBLISHER") "Altium Limited"))
      (libsource (lib "PCB_Project") (part "Res1_4"))
    )
    (comp (ref "R62")
      (value "Res1")
      (footprint "SMD_805")
      (description "Resistor")
      (fields (field (name "ALTIUM_VALUE") "22") (field (name "PUBLISHER") "Altium Limited"))
      (libsource (lib "PCB_Project") (part "Res1_4"))
    )
    (comp (ref "R63")
      (value "Res1")
      (footprint "SMD_805")
      (description "Resistor")
      (fields (field (name "ALTIUM_VALUE") "22") (field (name "PUBLISHER") "Altium Limited"))
      (libsource (lib "PCB_Project") (part "Res1_4"))
    )
    (comp (ref "R64")
      (value "Res1")
      (footprint "SMD_805")
      (description "Resistor")
      (fields (field (name "ALTIUM_VALUE") "22") (field (name "PUBLISHER") "Altium Limited"))
      (libsource (lib "PCB_Project") (part "Res1_4"))
    )
    (comp (ref "R65")
      (value "Res1")
      (footprint "SMD_805")
      (description "Resistor")
      (fields (field (name "ALTIUM_VALUE") "22") (field (name "PUBLISHER") "Altium Limited"))
      (libsource (lib "PCB_Project") (part "Res1_4"))
    )
    (comp (ref "R66")
      (value "Res1")
      (footprint "SMD_805")
      (description "Resistor")
      (fields (field (name "ALTIUM_VALUE") "220K") (field (name "PUBLISHER") "Altium Limited"))
      (libsource (lib "PCB_Project") (part "Res1_4"))
    )
    (comp (ref "R67")
      (value "Res1")
      (footprint "SMD_805")
      (description "Resistor")
      (fields (field (name "ALTIUM_VALUE") "0") (field (name "PUBLISHER") "Altium Limited"))
      (libsource (lib "PCB_Project") (part "Res1_4"))
    )
    (comp (ref "R68")
      (value "Res1")
      (footprint "SMD_805")
      (description "Resistor")
      (fields (field (name "ALTIUM_VALUE") "10K") (field (name "PUBLISHER") "Altium Limited"))
      (libsource (lib "PCB_Project") (part "Res1_6"))
    )
    (comp (ref "R69")
      (value "Res1")
      (footprint "SMD_805")
      (description "Resistor")
      (fields (field (name "ALTIUM_VALUE") "10K") (field (name "PUBLISHER") "Altium Limited"))
      (libsource (lib "PCB_Project") (part "Res1_6"))
    )
    (comp (ref "R70")
      (value "Res1")
      (footprint "SMD_805")
      (description "Resistor")
      (fields (field (name "ALTIUM_VALUE") "10K") (field (name "PUBLISHER") "Altium Limited"))
      (libsource (lib "PCB_Project") (part "Res1_6"))
    )
    (comp (ref "R71")
      (value "Res1")
      (footprint "SMD_805")
      (description "Resistor")
      (fields (field (name "ALTIUM_VALUE") "10K") (field (name "PUBLISHER") "Altium Limited"))
      (libsource (lib "PCB_Project") (part "Res1_6"))
    )
    (comp (ref "R72")
      (value "Res1")
      (footprint "SMD_805")
      (description "Resistor")
      (fields (field (name "ALTIUM_VALUE") "10K") (field (name "PUBLISHER") "Altium Limited"))
      (libsource (lib "PCB_Project") (part "Res1_6"))
    )
    (comp (ref "R73")
      (value "Res1")
      (footprint "SMD_805")
      (description "Resistor")
      (fields (field (name "ALTIUM_VALUE") "0") (field (name "PUBLISHER") "Altium Limited"))
      (libsource (lib "PCB_Project") (part "Res1_4"))
    )
    (comp (ref "R74")
      (value "Res1")
      (footprint "SMD_805")
      (description "Resistor")
      (fields (field (name "ALTIUM_VALUE") "0") (field (name "PUBLISHER") "Altium Limited"))
      (libsource (lib "PCB_Project") (part "Res1_4"))
    )
    (comp (ref "R75")
      (value "Res1")
      (footprint "SMD_805")
      (description "Resistor")
      (fields (field (name "ALTIUM_VALUE") "1.5K") (field (name "PUBLISHER") "Altium Limited"))
      (libsource (lib "PCB_Project") (part "Res1_8"))
    )
    (comp (ref "R76")
      (value "Res1")
      (footprint "SMD_805")
      (description "Resistor")
      (fields (field (name "ALTIUM_VALUE") "10K") (field (name "PUBLISHER") "Altium Limited"))
      (libsource (lib "PCB_Project") (part "Res1_6"))
    )
    (comp (ref "R77")
      (value "Res1")
      (footprint "SMD_805")
      (description "Resistor")
      (fields (field (name "ALTIUM_VALUE") "10K") (field (name "PUBLISHER") "Altium Limited"))
      (libsource (lib "PCB_Project") (part "Res1_6"))
    )
    (comp (ref "R78")
      (value "Res1")
      (footprint "SMD_805")
      (description "Resistor")
      (fields (field (name "ALTIUM_VALUE") "10K") (field (name "PUBLISHER") "Altium Limited"))
      (libsource (lib "PCB_Project") (part "Res1_6"))
    )
    (comp (ref "R79")
      (value "Res1")
      (footprint "SMD_805")
      (description "Resistor")
      (fields (field (name "ALTIUM_VALUE") "1.5K") (field (name "PUBLISHER") "Altium Limited"))
      (libsource (lib "PCB_Project") (part "Res1_8"))
    )
    (comp (ref "R80")
      (value "Res1")
      (footprint "SMD_805")
      (description "Resistor")
      (fields (field (name "ALTIUM_VALUE") "1.5K") (field (name "PUBLISHER") "Altium Limited"))
      (libsource (lib "PCB_Project") (part "Res1_8"))
    )
    (comp (ref "S1")
      (value "SW-PB")
      (footprint "RES_B")
      (description "Switch")
      (fields (field (name "PUBLISHER") "Altium Limited"))
      (libsource (lib "PCB_Project") (part "SW-PB"))
    )
    (comp (ref "S2")
      (value "SW-PB")
      (footprint "RES_B")
      (description "Switch")
      (fields (field (name "PUBLISHER") "Altium Limited"))
      (libsource (lib "PCB_Project") (part "SW-PB"))
    )
    (comp (ref "S3")
      (value "SW-PB")
      (footprint "RES_B")
      (description "Switch")
      (fields (field (name "PUBLISHER") "Altium Limited"))
      (libsource (lib "PCB_Project") (part "SW-PB"))
    )
    (comp (ref "S4")
      (value "SW-PB")
      (footprint "RES_B")
      (description "Switch")
      (fields (field (name "PUBLISHER") "Altium Limited"))
      (libsource (lib "PCB_Project") (part "SW-PB"))
    )
    (comp (ref "S5")
      (value "SW-SPST")
      (footprint "SPST-2")
      (description "Single-Pole, Single-Throw Switch")
      (fields (field (name "PUBLISHER") "Altium Limited"))
      (libsource (lib "Miscellaneous Devices") (part "SW-SPST"))
    )
    (comp (ref "S6")
      (value "SW-SPST")
      (footprint "SPST-2")
      (description "Single-Pole, Single-Throw Switch")
      (fields (field (name "PUBLISHER") "Altium Limited"))
      (libsource (lib "Miscellaneous Devices") (part "SW-SPST"))
    )
    (comp (ref "TP1")
      (value "TESTPOINT_PROBE")
      (footprint "TP80D50")
      (description "TEST POINT")
      (fields (field (name "MANF") "MANF") (field (name "MANF_P#") "MANF_P#"))
      (libsource (lib "test-tp_jumper") (part "TESTPOINT_PROBE"))
    )
    (comp (ref "U1")
      (value "DP83848CVV/NOPB")
      (footprint "QFP50P900X900X160-49N")
      (description "1/1 Transceiver - Ethernet 48-LQFP (7x7)")
      (fields (field (name "MF") "Texas Instruments") (field (name "MP") "DP83848CVV"))
      (libsource (lib "DP83848CVV_NOPB") (part "DP83848CVV/NOPB"))
    )
    (comp (ref "U2")
      (value "STMPS2141STR")
      (footprint "SOT95P280X145-5N")
      (description "Power Switch/Driver 1:1 N-Channel 500mA SOT-23-5")
      (fields (field (name "DIGI-KEY_PART_NUMBER") "497-6933-2-ND") (field (name "MF") "STMicroelectronics"))
      (libsource (lib "STMPS2141STR") (part "STMPS2141STR"))
    )
    (comp (ref "U3")
      (value "SN65HVD230QDR")
      (footprint "SOIC127P599X175-8N")
      (description "3.3-V CAN Transceiver with Standby Mode 8-SOIC -40 to 125")
      (fields (field (name "MF") "Texas Instruments"))
      (libsource (lib "SN65HVD230QDR") (part "SN65HVD230QDR"))
    )
    (comp (ref "U4")
      (value "M24C64-RMN6TP")
      (footprint "SOIC127P600X175-8N")
      (description "EEPROM Serial-I2C 64K-bit 8K x 8 2.5V/3.3V/5V 8-Pin SOIC T/R")
      (fields (field (name "MP") "altium_native_batch"))
      (libsource (lib "M24C64-RMN6TP") (part "M24C64-RMN6TP"))
    )
    (comp (ref "Y1")
      (value "ASDM1-24.000MHZ-LC-T")
      (footprint "SamacSys:ASDM")
      (description "Crystal or Oscillator")
      (fields (field (name "MOUSER PART NUMBER") "815-ASDM1-24.0-LCT"))
      (libsource (lib "*") (part "ASDM1-24.000MHZ-LC-T"))
    )
    (comp (ref "Y2")
      (value "ECS-250-18-5PX-JES-TR")
      (footprint "XTAL_ECS-250-18-5PX-JES-TR")
      (description "25MHz Â±20ppm Crystal 18pF 30 Ohms HC-49/US")
      (fields (field (name "MF") "ECS Inc."))
      (libsource (lib "ECS-250-18-5PX-JES-TR") (part "ECS-250-18-5PX-JES-TR"))
    )
    (comp (ref "Y3")
      (value "ECS-250-18-5PX-JES-TR")
      (footprint "XTAL_ECS-250-18-5PX-JES-TR")
      (description "25MHz Â±20ppm Crystal 18pF 30 Ohms HC-49/US")
      (fields (field (name "MF") "ECS Inc."))
      (libsource (lib "ECS-250-18-5PX-JES-TR") (part "ECS-250-18-5PX-JES-TR"))
    )
  )
  (nets
    (net (code "1") (name "+3V3") (class "Default")
      (node (ref "C1") (pin "2") (pinfunction "2_2") (pintype "passive"))
      (node (ref "C2") (pin "2") (pinfunction "2_2") (pintype "passive"))
      (node (ref "C23") (pin "1") (pinfunction "1_1") (pintype "passive"))
      (node (ref "C24") (pin "1") (pinfunction "1_1") (pintype "passive"))
      (node (ref "C26") (pin "2") (pinfunction "2_2") (pintype "passive"))
      (node (ref "C27") (pin "2") (pinfunction "2_2") (pintype "passive"))
      (node (ref "C28") (pin "2") (pinfunction "2_2") (pintype "passive"))
      (node (ref "C4") (pin "1") (pinfunction "1_1") (pintype "passive"))
      (node (ref "C41") (pin "2") (pinfunction "2_2") (pintype "passive"))
      (node (ref "C44") (pin "2") (pinfunction "2_2") (pintype "passive"))
      (node (ref "C7") (pin "1") (pinfunction "1_1") (pintype "passive"))
      (node (ref "D2") (pin "1") (pinfunction "A_1") (pintype "passive"))
      (node (ref "D3") (pin "2") (pinfunction "2_2") (pintype "passive"))
      (node (ref "IC1") (pin "2") (pinfunction "OUTPUT_1_2") (pintype "passive"))
      (node (ref "IC1") (pin "4") (pinfunction "OUTPUT_2_4") (pintype "passive"))
      (node (ref "IC3") (pin "31") (pinfunction "NRST_31") (pintype "input"))
      (node (ref "IC3") (pin "6") (pinfunction "VBAT_6") (pintype "passive"))
      (node (ref "J2") (pin "4") (pinfunction "4_4") (pintype "passive"))
      (node (ref "J3") (pin "4") (pinfunction "CT_1_4") (pintype "passive"))
      (node (ref "J3") (pin "5") (pinfunction "CT_2_5") (pintype "passive"))
      (node (ref "J5") (pin "1") (pinfunction "1_1") (pintype "passive"))
      (node (ref "J8") (pin "A1") (pinfunction "A1_A1") (pintype "passive"))
      (node (ref "J8") (pin "B1") (pinfunction "B1_B1") (pintype "passive"))
      (node (ref "J9") (pin "9") (pinfunction "9_9") (pintype "passive"))
      (node (ref "R1") (pin "1") (pinfunction "1_1") (pintype "passive"))
      (node (ref "R10") (pin "2") (pinfunction "2_2") (pintype "passive"))
      (node (ref "R11") (pin "1") (pinfunction "1_1") (pintype "passive"))
      (node (ref "R12") (pin "1") (pinfunction "1_1") (pintype "passive"))
      (node (ref "R12") (pin "2") (pinfunction "2_2") (pintype "passive"))
      (node (ref "R13") (pin "1") (pinfunction "1_1") (pintype "passive"))
      (node (ref "R16") (pin "1") (pinfunction "1_1") (pintype "passive"))
      (node (ref "R18") (pin "1") (pinfunction "1_1") (pintype "passive"))
      (node (ref "R2") (pin "1") (pinfunction "1_1") (pintype "passive"))
      (node (ref "R20") (pin "1") (pinfunction "1_1") (pintype "passive"))
      (node (ref "R23") (pin "1") (pinfunction "1_1") (pintype "passive"))
      (node (ref "R3") (pin "1") (pinfunction "1_1") (pintype "passive"))
      (node (ref "R4") (pin "1") (pinfunction "1_1") (pintype "passive"))
      (node (ref "R40") (pin "1") (pinfunction "1_1") (pintype "passive"))
      (node (ref "R41") (pin "1") (pinfunction "1_1") (pintype "passive"))
      (node (ref "R42") (pin "1") (pinfunction "1_1") (pintype "passive"))
      (node (ref "R46") (pin "2") (pinfunction "2_2") (pintype "passive"))
      (node (ref "R47") (pin "1") (pinfunction "1_1") (pintype "passive"))
      (node (ref "R48") (pin "1") (pinfunction "1_1") (pintype "passive"))
      (node (ref "R5") (pin "1") (pinfunction "1_1") (pintype "passive"))
      (node (ref "R50") (pin "1") (pinfunction "1_1") (pintype "passive"))
      (node (ref "R51") (pin "1") (pinfunction "1_1") (pintype "passive"))
      (node (ref "R52") (pin "2") (pinfunction "2_2") (pintype "passive"))
      (node (ref "R53") (pin "2") (pinfunction "2_2") (pintype "passive"))
      (node (ref "R54") (pin "2") (pinfunction "2_2") (pintype "passive"))
      (node (ref "R59") (pin "1") (pinfunction "1_1") (pintype "passive"))
      (node (ref "R6") (pin "2") (pinfunction "2_2") (pintype "passive"))
      (node (ref "R65") (pin "1") (pinfunction "1_1") (pintype "passive"))
      (node (ref "R67") (pin "2") (pinfunction "2_2") (pintype "passive"))
      (node (ref "R7") (pin "2") (pinfunction "2_2") (pintype "passive"))
      (node (ref "R8") (pin "2") (pinfunction "2_2") (pintype "passive"))
      (node (ref "R9") (pin "2") (pinfunction "2_2") (pintype "passive"))
      (node (ref "S1") (pin "2") (pinfunction "2_2") (pintype "passive"))
      (node (ref "S4") (pin "1") (pinfunction "1_1") (pintype "passive"))
      (node (ref "S5") (pin "1") (pinfunction "COMMON_1") (pintype "passive"))
      (node (ref "S6") (pin "1") (pinfunction "COMMON_1") (pintype "passive"))
      (node (ref "U1") (pin "22") (pinfunction "AVDD33_22") (pintype "power_in"))
      (node (ref "U1") (pin "29") (pinfunction "~{RESET}_29") (pintype "input"))
      (node (ref "U1") (pin "32") (pinfunction "IOVDD33_32") (pintype "power_in"))
      (node (ref "U1") (pin "48") (pinfunction "IOVDD33_48") (pintype "power_in"))
      (node (ref "U3") (pin "3") (pinfunction "VCC_3") (pintype "power_in"))
      (node (ref "U4") (pin "8") (pinfunction "VCC_8") (pintype "power_in"))
      (node (ref "Y1") (pin "4") (pinfunction "VDD_4") (pintype "passive"))
    )
    (net (code "2") (name "/+5V") (class "Default")
      (node (ref "C3") (pin "1") (pinfunction "1_1") (pintype "passive"))
      (node (ref "C5") (pin "1") (pinfunction "1_1") (pintype "passive"))
      (node (ref "FL1") (pin "2") (pinfunction "CB_2") (pintype "passive"))
      (node (ref "IC1") (pin "3") (pinfunction "INPUT_3") (pintype "passive"))
      (node (ref "U2") (pin "5") (pinfunction "IN_5") (pintype "input"))
    )
    (net (code "3") (name "/Anti_Tamper") (class "Default")
      (node (ref "C22") (pin "1") (pinfunction "1_1") (pintype "passive"))
      (node (ref "IC3") (pin "8") (pinfunction "PC13_8") (pintype "passive"))
      (node (ref "R20") (pin "2") (pinfunction "2_2") (pintype "passive"))
      (node (ref "S2") (pin "2") (pinfunction "2_2") (pintype "passive"))
    )
    (net (code "4") (name "/BOOT0") (class "Default")
      (node (ref "IC3") (pin "166") (pinfunction "BOOT0_166") (pintype "passive"))
      (node (ref "R71") (pin "1") (pinfunction "1_1") (pintype "passive"))
      (node (ref "S5") (pin "2") (pinfunction "NO_2") (pintype "passive"))
    )
    (net (code "5") (name "/CAN_RX") (class "Default")
      (node (ref "IC3") (pin "163") (pinfunction "PB5_163") (pintype "passive"))
      (node (ref "U3") (pin "4") (pinfunction "R_4") (pintype "output"))
    )
    (net (code "6") (name "/CAN_TX") (class "Default")
      (node (ref "IC3") (pin "93") (pinfunction "PB13_93") (pintype "passive"))
      (node (ref "U3") (pin "1") (pinfunction "D_1") (pintype "input"))
    )
    (net (code "7") (name "/D0") (class "Default")
      (node (ref "IC3") (pin "86") (pinfunction "PH9_86") (pintype "passive"))
      (node (ref "J5") (pin "16") (pinfunction "16_16") (pintype "passive"))
    )
    (net (code "8") (name "/D1") (class "Default")
      (node (ref "IC3") (pin "87") (pinfunction "PH10_87") (pintype "passive"))
      (node (ref "J5") (pin "15") (pinfunction "15_15") (pintype "passive"))
    )
    (net (code "9") (name "/D2") (class "Default")
      (node (ref "IC3") (pin "88") (pinfunction "PH11_88") (pintype "passive"))
      (node (ref "J5") (pin "14") (pinfunction "14_14") (pintype "passive"))
    )
    (net (code "10") (name "/D3") (class "Default")
      (node (ref "IC3") (pin "89") (pinfunction "PH12_89") (pintype "passive"))
      (node (ref "J5") (pin "13") (pinfunction "13_13") (pintype "passive"))
    )
    (net (code "11") (name "/D4") (class "Default")
      (node (ref "IC3") (pin "129") (pinfunction "PH14_129") (pintype "passive"))
      (node (ref "J5") (pin "12") (pinfunction "12_12") (pintype "passive"))
    )
    (net (code "12") (name "/D5") (class "Default")
      (node (ref "IC3") (pin "173") (pinfunction "PI4_173") (pintype "passive"))
      (node (ref "J5") (pin "11") (pinfunction "11_11") (pintype "passive"))
    )
    (net (code "13") (name "/D6") (class "Default")
      (node (ref "IC3") (pin "175") (pinfunction "PI6_175") (pintype "passive"))
      (node (ref "J5") (pin "10") (pinfunction "10_10") (pintype "passive"))
    )
    (net (code "14") (name "/D7") (class "Default")
      (node (ref "IC3") (pin "176") (pinfunction "PI7_176") (pintype "passive"))
      (node (ref "J5") (pin "9") (pinfunction "9_9") (pintype "passive"))
    )
    (net (code "15") (name "/EEPROM_SCL") (class "Default")
      (node (ref "IC3") (pin "164") (pinfunction "PB6_164") (pintype "passive"))
      (node (ref "U4") (pin "6") (pinfunction "SCL_6") (pintype "input"))
    )
    (net (code "16") (name "/EEPROM_SDA") (class "Default")
      (node (ref "IC3") (pin "168") (pinfunction "PB9_168") (pintype "passive"))
      (node (ref "U4") (pin "5") (pinfunction "SDA_5") (pintype "bidirectional"))
    )
    (net (code "17") (name "/HREF_Cam") (class "Default")
      (node (ref "IC3") (pin "85") (pinfunction "PH8_85") (pintype "passive"))
      (node (ref "J5") (pin "6") (pinfunction "6_6") (pintype "passive"))
    )
    (net (code "18") (name "/LED0") (class "Default")
      (node (ref "D9") (pin "1") (pinfunction "A_1") (pintype "passive"))
      (node (ref "IC3") (pin "116") (pinfunction "PC7_116") (pintype "passive"))
    )
    (net (code "19") (name "/LED1") (class "Default")
      (node (ref "D10") (pin "1") (pinfunction "A_1") (pintype "passive"))
      (node (ref "IC3") (pin "112") (pinfunction "PG8_112") (pintype "passive"))
    )
    (net (code "20") (name "/LED2") (class "Default")
      (node (ref "D11") (pin "1") (pinfunction "A_1") (pintype "passive"))
      (node (ref "IC3") (pin "110") (pinfunction "PG6_110") (pintype "passive"))
    )
    (net (code "21") (name "/LED_Yellow_K") (class "Default")
      (node (ref "J3") (pin "11") (pinfunction "K_YELLOW_11") (pintype "passive"))
      (node (ref "R40") (pin "2") (pinfunction "2_2") (pintype "passive"))
      (node (ref "U1") (pin "26") (pinfunction "LED_ACT/COL/AN_EN_26") (pintype "output"))
    )
    (net (code "22") (name "/LED_green_K") (class "Default")
      (node (ref "J3") (pin "10") (pinfunction "K_GREEN_10") (pintype "passive"))
      (node (ref "R42") (pin "2") (pinfunction "2_2") (pintype "passive"))
      (node (ref "U1") (pin "28") (pinfunction "LED_LINK/AN0_28") (pintype "output"))
    )
    (net (code "23") (name "/MCO") (class "Default")
      (node (ref "IC3") (pin "119") (pinfunction "PA8_119") (pintype "passive"))
      (node (ref "R56") (pin "1") (pinfunction "1_1") (pintype "passive"))
      (node (ref "TP1") (pin "1") (pinfunction "1_1") (pintype "passive"))
    )
    (net (code "24") (name "/MDIO") (class "Default")
      (node (ref "R21") (pin "2") (pinfunction "2_2") (pintype "passive"))
      (node (ref "R23") (pin "2") (pinfunction "2_2") (pintype "passive"))
      (node (ref "U1") (pin "30") (pinfunction "MDIO_30") (pintype "bidirectional"))
    )
    (net (code "25") (name "/MII_COL") (class "Default")
      (node (ref "IC3") (pin "44") (pinfunction "PH3_44") (pintype "passive"))
      (node (ref "R45") (pin "2") (pinfunction "2_2") (pintype "passive"))
    )
    (net (code "26") (name "/MII_CRS") (class "Default")
      (node (ref "IC3") (pin "43") (pinfunction "PH2_43") (pintype "passive"))
      (node (ref "R44") (pin "2") (pinfunction "2_2") (pintype "passive"))
    )
    (net (code "27") (name "/MII_INT") (class "Default")
      (node (ref "IC3") (pin "94") (pinfunction "PB14_94") (pintype "passive"))
      (node (ref "R17") (pin "1") (pinfunction "1_1") (pintype "passive"))
    )
    (net (code "28") (name "/MII_MDC") (class "Default")
      (node (ref "IC3") (pin "33") (pinfunction "PC1_33") (pintype "passive"))
      (node (ref "U1") (pin "31") (pinfunction "MDC_31") (pintype "input"))
    )
    (net (code "29") (name "/MII_MDIO") (class "Default")
      (node (ref "IC3") (pin "42") (pinfunction "PA2_42") (pintype "passive"))
      (node (ref "R21") (pin "1") (pinfunction "1_1") (pintype "passive"))
    )
    (net (code "30") (name "/MII_RXD0") (class "Default")
      (node (ref "IC3") (pin "54") (pinfunction "PC4_54") (pintype "passive"))
      (node (ref "R27") (pin "2") (pinfunction "2_2") (pintype "passive"))
    )
    (net (code "31") (name "/MII_RXD1") (class "Default")
      (node (ref "IC3") (pin "55") (pinfunction "PC5_55") (pintype "passive"))
      (node (ref "R30") (pin "2") (pinfunction "2_2") (pintype "passive"))
    )
    (net (code "32") (name "/MII_RXD2") (class "Default")
      (node (ref "IC3") (pin "83") (pinfunction "PH6_83") (pintype "passive"))
      (node (ref "R33") (pin "2") (pinfunction "2_2") (pintype "passive"))
    )
    (net (code "33") (name "/MII_RXD3") (class "Default")
      (node (ref "IC3") (pin "84") (pinfunction "PH7_84") (pintype "passive"))
      (node (ref "R35") (pin "2") (pinfunction "2_2") (pintype "passive"))
    )
    (net (code "34") (name "/MII_RX_CLK") (class "Default")
      (node (ref "IC3") (pin "41") (pinfunction "PA1_41") (pintype "passive"))
      (node (ref "J4") (pin "2") (pinfunction "2_2") (pintype "passive"))
    )
    (net (code "35") (name "/MII_RX_DV") (class "Default")
      (node (ref "IC3") (pin "53") (pinfunction "PA7_53") (pintype "passive"))
      (node (ref "R36") (pin "2") (pinfunction "2_2") (pintype "passive"))
    )
    (net (code "36") (name "/MII_RX_ER") (class "Default")
      (node (ref "IC3") (pin "12") (pinfunction "PI10_12") (pintype "passive"))
      (node (ref "R39") (pin "2") (pinfunction "2_2") (pintype "passive"))
    )
    (net (code "37") (name "/MII_TXD0") (class "Default")
      (node (ref "IC3") (pin "156") (pinfunction "PG13_156") (pintype "passive"))
      (node (ref "R24") (pin "1") (pinfunction "1_1") (pintype "passive"))
    )
    (net (code "38") (name "/MII_TXD1") (class "Default")
      (node (ref "IC3") (pin "157") (pinfunction "PG14_157") (pintype "passive"))
      (node (ref "R25") (pin "1") (pinfunction "1_1") (pintype "passive"))
    )
    (net (code "39") (name "/MII_TXD2") (class "Default")
      (node (ref "IC3") (pin "34") (pinfunction "PC2_34") (pintype "passive"))
      (node (ref "R26") (pin "1") (pinfunction "1_1") (pintype "passive"))
    )
    (net (code "40") (name "/MII_TXD3") (class "Default")
      (node (ref "IC3") (pin "167") (pinfunction "PB8_167") (pintype "passive"))
      (node (ref "R29") (pin "1") (pinfunction "1_1") (pintype "passive"))
    )
    (net (code "41") (name "/MII_TX_CLK") (class "Default")
      (node (ref "IC3") (pin "35") (pinfunction "PC3_35") (pintype "passive"))
      (node (ref "R34") (pin "1") (pinfunction "1_1") (pintype "passive"))
    )
    (net (code "42") (name "/MII_TX_EN") (class "Default")
      (node (ref "IC3") (pin "154") (pinfunction "PG11_154") (pintype "passive"))
      (node (ref "R32") (pin "1") (pinfunction "1_1") (pintype "passive"))
    )
    (net (code "43") (name "/MicroSDCard_CLK") (class "Default")
      (node (ref "IC3") (pin "141") (pinfunction "PC12_141") (pintype "passive"))
      (node (ref "J2") (pin "5") (pinfunction "5_5") (pintype "passive"))
    )
    (net (code "44") (name "/MicroSDCard_CMD") (class "Default")
      (node (ref "IC3") (pin "144") (pinfunction "PD2_144") (pintype "passive"))
      (node (ref "J2") (pin "3") (pinfunction "3_3") (pintype "passive"))
      (node (ref "R3") (pin "2") (pinfunction "2_2") (pintype "passive"))
    )
    (net (code "45") (name "/MicroSDCard_D0") (class "Default")
      (node (ref "IC3") (pin "117") (pinfunction "PC8_117") (pintype "passive"))
      (node (ref "J2") (pin "7") (pinfunction "7_7") (pintype "passive"))
      (node (ref "R4") (pin "2") (pinfunction "2_2") (pintype "passive"))
    )
    (net (code "46") (name "/MicroSDCard_D1") (class "Default")
      (node (ref "IC3") (pin "118") (pinfunction "PC9_118") (pintype "passive"))
      (node (ref "J2") (pin "8") (pinfunction "8_8") (pintype "passive"))
      (node (ref "R5") (pin "2") (pinfunction "2_2") (pintype "passive"))
    )
    (net (code "47") (name "/MicroSDCard_D2") (class "Default")
      (node (ref "IC3") (pin "139") (pinfunction "PC10_139") (pintype "passive"))
      (node (ref "J2") (pin "1") (pinfunction "1_1") (pintype "passive"))
      (node (ref "R1") (pin "2") (pinfunction "2_2") (pintype "passive"))
    )
    (net (code "48") (name "/MicroSDCard_D3") (class "Default")
      (node (ref "IC3") (pin "140") (pinfunction "PC11_140") (pintype "passive"))
      (node (ref "J2") (pin "2") (pinfunction "2_2") (pintype "passive"))
      (node (ref "R2") (pin "2") (pinfunction "2_2") (pintype "passive"))
    )
    (net (code "49") (name "/MicroSDCard_Detect") (class "Default")
      (node (ref "IC3") (pin "128") (pinfunction "PH13_128") (pintype "passive"))
      (node (ref "R15") (pin "2") (pinfunction "2_2") (pintype "passive"))
    )
    (net (code "50") (name "/OTG_FS_DM") (class "Default")
      (node (ref "IC2") (pin "D3") (pinfunction "D-OUT_D3") (pintype "passive"))
      (node (ref "IC3") (pin "122") (pinfunction "PA11_122") (pintype "passive"))
      (node (ref "R37") (pin "2") (pinfunction "2_2") (pintype "passive"))
    )
    (net (code "51") (name "/OTG_FS_DP") (class "Default")
      (node (ref "IC2") (pin "C3") (pinfunction "D+OUT_C3") (pintype "passive"))
      (node (ref "IC3") (pin "123") (pinfunction "PA12_123") (pintype "passive"))
      (node (ref "R28") (pin "2") (pinfunction "2_2") (pintype "passive"))
    )
    (net (code "52") (name "/OTG_FS_ID") (class "Default")
      (node (ref "IC3") (pin "121") (pinfunction "PA10_121") (pintype "passive"))
      (node (ref "R31") (pin "2") (pinfunction "2_2") (pintype "passive"))
    )
    (net (code "53") (name "/OTG_FS_OverCurrent") (class "Default")
      (node (ref "IC3") (pin "59") (pinfunction "PF11_59") (pintype "passive"))
      (node (ref "R58") (pin "2") (pinfunction "2_2") (pintype "passive"))
    )
    (net (code "54") (name "/OTG_FS_PowerSwitchOn") (class "Default")
      (node (ref "IC3") (pin "46") (pinfunction "PH5_46") (pintype "passive"))
      (node (ref "R55") (pin "1") (pinfunction "1_1") (pintype "passive"))
    )
    (net (code "55") (name "/PA0_WKUP") (class "Default")
      (node (ref "C35") (pin "1") (pinfunction "1_1") (pintype "passive"))
      (node (ref "IC3") (pin "40") (pinfunction "PA0_40") (pintype "passive"))
      (node (ref "R66") (pin "2") (pinfunction "2_2") (pintype "passive"))
      (node (ref "S4") (pin "2") (pinfunction "2_2") (pintype "passive"))
    )
    (net (code "56") (name "/PB2_BOOT1") (class "Default")
      (node (ref "IC3") (pin "58") (pinfunction "PB2_58") (pintype "passive"))
      (node (ref "R72") (pin "1") (pinfunction "1_1") (pintype "passive"))
      (node (ref "S6") (pin "2") (pinfunction "NO_2") (pintype "passive"))
    )
    (net (code "57") (name "/PCLK_Cam") (class "Default")
      (node (ref "IC3") (pin "52") (pinfunction "PA6_52") (pintype "passive"))
      (node (ref "J5") (pin "7") (pinfunction "7_7") (pintype "passive"))
    )
    (net (code "58") (name "/PWR_DOWN{slash}INT") (class "Default")
      (node (ref "R17") (pin "2") (pinfunction "2_2") (pintype "passive"))
      (node (ref "R18") (pin "2") (pinfunction "2_2") (pintype "passive"))
      (node (ref "U1") (pin "7") (pinfunction "PWR_DOWN/INT_7") (pintype "input"))
    )
    (net (code "59") (name "/RD+") (class "Default")
      (node (ref "J3") (pin "3") (pinfunction "RD+_3") (pintype "passive"))
      (node (ref "R8") (pin "1") (pinfunction "1_1") (pintype "passive"))
      (node (ref "U1") (pin "14") (pinfunction "RD+_14") (pintype "bidirectional"))
    )
    (net (code "60") (name "/RD-") (class "Default")
      (node (ref "J3") (pin "6") (pinfunction "RD-_6") (pintype "passive"))
      (node (ref "R9") (pin "1") (pinfunction "1_1") (pintype "passive"))
      (node (ref "U1") (pin "13") (pinfunction "RD-_13") (pintype "bidirectional"))
    )
    (net (code "61") (name "/RESET_Con") (class "Default")
      (node (ref "J8") (pin "B8") (pinfunction "B8_B8") (pintype "passive"))
      (node (ref "R65") (pin "2") (pinfunction "2_2") (pintype "passive"))
    )
    (net (code "62") (name "/SCL_Cam") (class "Default")
      (node (ref "IC3") (pin "17") (pinfunction "PF1_17") (pintype "passive"))
      (node (ref "J5") (pin "3") (pinfunction "3_3") (pintype "passive"))
    )
    (net (code "63") (name "/SDA_Cam") (class "Default")
      (node (ref "IC3") (pin "16") (pinfunction "PF0_16") (pintype "passive"))
      (node (ref "J5") (pin "4") (pinfunction "4_4") (pintype "passive"))
    )
    (net (code "64") (name "/TCK{slash}SWCLK") (class "Default")
      (node (ref "D5") (pin "2") (pinfunction "2_2") (pintype "passive"))
      (node (ref "IC3") (pin "137") (pinfunction "PA14_137") (pintype "passive"))
      (node (ref "R63") (pin "1") (pinfunction "1_1") (pintype "passive"))
    )
    (net (code "65") (name "/TCK{slash}SWCLK_Con") (class "Default")
      (node (ref "J8") (pin "B5") (pinfunction "B5_B5") (pintype "passive"))
      (node (ref "R63") (pin "2") (pinfunction "2_2") (pintype "passive"))
    )
    (net (code "66") (name "/TD+") (class "Default")
      (node (ref "J3") (pin "1") (pinfunction "TD+_1") (pintype "passive"))
      (node (ref "R6") (pin "1") (pinfunction "1_1") (pintype "passive"))
      (node (ref "U1") (pin "17") (pinfunction "TD+_17") (pintype "bidirectional"))
    )
    (net (code "67") (name "/TD-") (class "Default")
      (node (ref "J3") (pin "2") (pinfunction "TD-_2") (pintype "passive"))
      (node (ref "R7") (pin "1") (pinfunction "1_1") (pintype "passive"))
      (node (ref "U1") (pin "16") (pinfunction "TD-_16") (pintype "bidirectional"))
    )
    (net (code "68") (name "/TDI") (class "Default")
      (node (ref "D7") (pin "2") (pinfunction "2_2") (pintype "passive"))
      (node (ref "IC3") (pin "138") (pinfunction "PA15_138") (pintype "passive"))
      (node (ref "R61") (pin "1") (pinfunction "1_1") (pintype "passive"))
    )
    (net (code "69") (name "/TDI_Con") (class "Default")
      (node (ref "J8") (pin "B3") (pinfunction "B3_B3") (pintype "passive"))
      (node (ref "R61") (pin "2") (pinfunction "2_2") (pintype "passive"))
    )
    (net (code "70") (name "/TDO{slash}SWO") (class "Default")
      (node (ref "D4") (pin "2") (pinfunction "2_2") (pintype "passive"))
      (node (ref "IC3") (pin "161") (pinfunction "PB3_161") (pintype "passive"))
      (node (ref "R64") (pin "1") (pinfunction "1_1") (pintype "passive"))
    )
    (net (code "71") (name "/TDO{slash}SWO_Con") (class "Default")
      (node (ref "J8") (pin "B7") (pinfunction "B7_B7") (pintype "passive"))
      (node (ref "R64") (pin "2") (pinfunction "2_2") (pintype "passive"))
    )
    (net (code "72") (name "/TMS{slash}SWDIO") (class "Default")
      (node (ref "D6") (pin "2") (pinfunction "2_2") (pintype "passive"))
      (node (ref "IC3") (pin "124") (pinfunction "PA13_124") (pintype "passive"))
      (node (ref "R62") (pin "1") (pinfunction "1_1") (pintype "passive"))
    )
    (net (code "73") (name "/TMS{slash}SWDIO_Con") (class "Default")
      (node (ref "J8") (pin "B4") (pinfunction "B4_B4") (pintype "passive"))
      (node (ref "R62") (pin "2") (pinfunction "2_2") (pintype "passive"))
    )
    (net (code "74") (name "/TRST") (class "Default")
      (node (ref "D8") (pin "2") (pinfunction "2_2") (pintype "passive"))
      (node (ref "IC3") (pin "162") (pinfunction "PB4_162") (pintype "passive"))
      (node (ref "R60") (pin "1") (pinfunction "1_1") (pintype "passive"))
    )
    (net (code "75") (name "/TRST_Con") (class "Default")
      (node (ref "J8") (pin "B2") (pinfunction "B2_B2") (pintype "passive"))
      (node (ref "R60") (pin "2") (pinfunction "2_2") (pintype "passive"))
    )
    (net (code "76") (name "/User_Button") (class "Default")
      (node (ref "C34") (pin "1") (pinfunction "1_1") (pintype "passive"))
      (node (ref "IC3") (pin "160") (pinfunction "PG15_160") (pintype "passive"))
      (node (ref "R50") (pin "2") (pinfunction "2_2") (pintype "passive"))
      (node (ref "S3") (pin "2") (pinfunction "2_2") (pintype "passive"))
    )
    (net (code "77") (name "/VDDA") (class "Default")
      (node (ref "C36") (pin "1") (pinfunction "1_1") (pintype "passive"))
      (node (ref "C37") (pin "2") (pinfunction "2_2") (pintype "passive"))
      (node (ref "C39") (pin "1") (pinfunction "1_1") (pintype "passive"))
      (node (ref "C40") (pin "2") (pinfunction "2_2") (pintype "passive"))
      (node (ref "FL2") (pin "2") (pinfunction "2_2") (pintype "passive"))
      (node (ref "IC3") (pin "38") (pinfunction "VREF+_38") (pintype "input"))
      (node (ref "IC3") (pin "39") (pinfunction "VDDA_39") (pintype "power_in"))
    )
    (net (code "78") (name "/VSYNC_Cam") (class "Default")
      (node (ref "IC3") (pin "174") (pinfunction "PI5_174") (pintype "passive"))
      (node (ref "J5") (pin "5") (pinfunction "5_5") (pintype "passive"))
    )
    (net (code "79") (name "/WC_B") (class "Default")
      (node (ref "IC3") (pin "11") (pinfunction "PI9_11") (pintype "passive"))
      (node (ref "R78") (pin "1") (pinfunction "1_1") (pintype "passive"))
    )
    (net (code "80") (name "/X1") (class "Default")
      (node (ref "J7") (pin "2") (pinfunction "2_2") (pintype "passive"))
      (node (ref "U1") (pin "34") (pinfunction "X1_34") (pintype "input"))
    )
    (net (code "81") (name "/X2") (class "Default")
      (node (ref "R49") (pin "1") (pinfunction "1_1") (pintype "passive"))
      (node (ref "U1") (pin "33") (pinfunction "X2_33") (pintype "output"))
    )
    (net (code "82") (name "/XCLK_Cam") (class "Default")
      (node (ref "J5") (pin "8") (pinfunction "8_8") (pintype "passive"))
      (node (ref "Y1") (pin "3") (pinfunction "OUTPUT_3") (pintype "passive"))
    )
    (net (code "83") (name "GND") (class "Default")
      (node (ref "C1") (pin "1") (pinfunction "1_1") (pintype "passive"))
      (node (ref "C10") (pin "1") (pinfunction "1_1") (pintype "passive"))
      (node (ref "C11") (pin "1") (pinfunction "1_1") (pintype "passive"))
      (node (ref "C12") (pin "1") (pinfunction "1_1") (pintype "passive"))
      (node (ref "C13") (pin "1") (pinfunction "1_1") (pintype "passive"))
      (node (ref "C14") (pin "1") (pinfunction "1_1") (pintype "passive"))
      (node (ref "C15") (pin "1") (pinfunction "1_1") (pintype "passive"))
      (node (ref "C16") (pin "1") (pinfunction "1_1") (pintype "passive"))
      (node (ref "C17") (pin "1") (pinfunction "1_1") (pintype "passive"))
      (node (ref "C18") (pin "1") (pinfunction "1_1") (pintype "passive"))
      (node (ref "C19") (pin "1") (pinfunction "1_1") (pintype "passive"))
      (node (ref "C2") (pin "1") (pinfunction "1_1") (pintype "passive"))
      (node (ref "C20") (pin "1") (pinfunction "1_1") (pintype "passive"))
      (node (ref "C21") (pin "1") (pinfunction "1_1") (pintype "passive"))
      (node (ref "C23") (pin "2") (pinfunction "2_2") (pintype "passive"))
      (node (ref "C24") (pin "2") (pinfunction "2_2") (pintype "passive"))
      (node (ref "C25") (pin "2") (pinfunction "2_2") (pintype "passive"))
      (node (ref "C26") (pin "1") (pinfunction "1_1") (pintype "passive"))
      (node (ref "C27") (pin "1") (pinfunction "1_1") (pintype "passive"))
      (node (ref "C28") (pin "1") (pinfunction "1_1") (pintype "passive"))
      (node (ref "C29") (pin "1") (pinfunction "1_1") (pintype "passive"))
      (node (ref "C3") (pin "2") (pinfunction "2_2") (pintype "passive"))
      (node (ref "C30") (pin "1") (pinfunction "1_1") (pintype "passive"))
      (node (ref "C31") (pin "1") (pinfunction "1_1") (pintype "passive"))
      (node (ref "C32") (pin "2") (pinfunction "2_2") (pintype "passive"))
      (node (ref "C33") (pin "2") (pinfunction "2_2") (pintype "passive"))
      (node (ref "C36") (pin "2") (pinfunction "2_2") (pintype "passive"))
      (node (ref "C37") (pin "1") (pinfunction "1_1") (pintype "passive"))
      (node (ref "C38") (pin "2") (pinfunction "2_2") (pintype "passive"))
      (node (ref "C39") (pin "2") (pinfunction "2_2") (pintype "passive"))
      (node (ref "C4") (pin "2") (pinfunction "2_2") (pintype "passive"))
      (node (ref "C40") (pin "1") (pinfunction "1_1") (pintype "passive"))
      (node (ref "C41") (pin "1") (pinfunction "1_1") (pintype "passive"))
      (node (ref "C42") (pin "2") (pinfunction "2_2") (pintype "passive"))
      (node (ref "C43") (pin "2") (pinfunction "2_2") (pintype "passive"))
      (node (ref "C44") (pin "1") (pinfunction "1_1") (pintype "passive"))
      (node (ref "C45") (pin "2") (pinfunction "2_2") (pintype "passive"))
      (node (ref "C5") (pin "2") (pinfunction "2_2") (pintype "passive"))
      (node (ref "C7") (pin "2") (pinfunction "2_2") (pintype "passive"))
      (node (ref "C8") (pin "1") (pinfunction "1_1") (pintype "passive"))
      (node (ref "C9") (pin "1") (pinfunction "1_1") (pintype "passive"))
      (node (ref "D3") (pin "1") (pinfunction "1_1") (pintype "passive"))
      (node (ref "D4") (pin "1") (pinfunction "1_1") (pintype "passive"))
      (node (ref "D5") (pin "1") (pinfunction "1_1") (pintype "passive"))
      (node (ref "D6") (pin "1") (pinfunction "1_1") (pintype "passive"))
      (node (ref "D7") (pin "1") (pinfunction "1_1") (pintype "passive"))
      (node (ref "D8") (pin "1") (pinfunction "1_1") (pintype "passive"))
      (node (ref "FL1") (pin "4") (pinfunction "CG_4") (pintype "passive"))
      (node (ref "FL1") (pin "5") (pinfunction "CG_5") (pintype "passive"))
      (node (ref "FL1") (pin "6") (pinfunction "CG_6") (pintype "passive"))
      (node (ref "IC3") (pin "102") (pinfunction "VSS_6_102") (pintype "power_in"))
      (node (ref "IC3") (pin "113") (pinfunction "VSS_7_113") (pintype "power_in"))
      (node (ref "IC3") (pin "126") (pinfunction "VSS_8_126") (pintype "power_in"))
      (node (ref "IC3") (pin "135") (pinfunction "VSS_9_135") (pintype "power_in"))
      (node (ref "IC3") (pin "14") (pinfunction "VSS_1_14") (pintype "power_in"))
      (node (ref "IC3") (pin "148") (pinfunction "VSS_10_148") (pintype "power_in"))
      (node (ref "IC3") (pin "158") (pinfunction "VSS_11_158") (pintype "power_in"))
      (node (ref "IC3") (pin "22") (pinfunction "VSS_2_22") (pintype "power_in"))
      (node (ref "IC3") (pin "37") (pinfunction "VSSA_37") (pintype "power_in"))
      (node (ref "IC3") (pin "61") (pinfunction "VSS_3_61") (pintype "power_in"))
      (node (ref "IC3") (pin "71") (pinfunction "VSS_4_71") (pintype "power_in"))
      (node (ref "IC3") (pin "90") (pinfunction "VSS_5_90") (pintype "power_in"))
      (node (ref "J2") (pin "11") (pinfunction "COMM_11") (pintype "passive"))
      (node (ref "J2") (pin "12") (pinfunction "WP_12") (pintype "passive"))
      (node (ref "J2") (pin "6") (pinfunction "6_6") (pintype "passive"))
      (node (ref "J2") (pin "9") (pinfunction "9_9") (pintype "passive"))
      (node (ref "J2") (pin "SH1") (pinfunction "SHIELD_SH1") (pintype "passive"))
      (node (ref "J2") (pin "SH2") (pinfunction "SHIELD_SH2") (pintype "passive"))
      (node (ref "J3") (pin "8") (pinfunction "CHS_GROUND_8") (pintype "passive"))
      (node (ref "J3") (pin "MH3") (pinfunction "MH3_MH3") (pintype "passive"))
      (node (ref "J3") (pin "MH4") (pinfunction "MH4_MH4") (pintype "passive"))
      (node (ref "J5") (pin "2") (pinfunction "2_2") (pintype "passive"))
      (node (ref "J6") (pin "10") (pinfunction "MNT_5_10") (pintype "passive"))
      (node (ref "J6") (pin "5") (pinfunction "GND_5") (pintype "power_in"))
      (node (ref "J6") (pin "6") (pinfunction "MNT_1_6") (pintype "passive"))
      (node (ref "J6") (pin "7") (pinfunction "MNT_2_7") (pintype "passive"))
      (node (ref "J6") (pin "8") (pinfunction "MNT_3_8") (pintype "passive"))
      (node (ref "J6") (pin "9") (pinfunction "MNT_4_9") (pintype "passive"))
      (node (ref "J8") (pin "A10") (pinfunction "A10_A10") (pintype "passive"))
      (node (ref "J8") (pin "A2") (pinfunction "A2_A2") (pintype "passive"))
      (node (ref "J8") (pin "A3") (pinfunction "A3_A3") (pintype "passive"))
      (node (ref "J8") (pin "A4") (pinfunction "A4_A4") (pintype "passive"))
      (node (ref "J8") (pin "A5") (pinfunction "A5_A5") (pintype "passive"))
      (node (ref "J8") (pin "A6") (pinfunction "A6_A6") (pintype "passive"))
      (node (ref "J8") (pin "A7") (pinfunction "A7_A7") (pintype "passive"))
      (node (ref "J8") (pin "A8") (pinfunction "A8_A8") (pintype "passive"))
      (node (ref "J8") (pin "A9") (pinfunction "A9_A9") (pintype "passive"))
      (node (ref "J9") (pin "10") (pinfunction "MH1_10") (pintype "passive"))
      (node (ref "J9") (pin "11") (pinfunction "MH2_11") (pintype "passive"))
      (node (ref "J9") (pin "2") (pinfunction "2_2") (pintype "passive"))
      (node (ref "J9") (pin "4") (pinfunction "4_4") (pintype "passive"))
      (node (ref "J9") (pin "5") (pinfunction "5_5") (pintype "passive"))
      (node (ref "J9") (pin "8") (pinfunction "8_8") (pintype "passive"))
      (node (ref "R14") (pin "1") (pinfunction "1_1") (pintype "passive"))
      (node (ref "R38") (pin "1") (pinfunction "1_1") (pintype "passive"))
      (node (ref "R43") (pin "1") (pinfunction "1_1") (pintype "passive"))
      (node (ref "R57") (pin "1") (pinfunction "1_1") (pintype "passive"))
      (node (ref "R66") (pin "1") (pinfunction "1_1") (pintype "passive"))
      (node (ref "R68") (pin "1") (pinfunction "1_1") (pintype "passive"))
      (node (ref "R69") (pin "1") (pinfunction "1_1") (pintype "passive"))
      (node (ref "R70") (pin "1") (pinfunction "1_1") (pintype "passive"))
      (node (ref "R71") (pin "2") (pinfunction "2_2") (pintype "passive"))
      (node (ref "R72") (pin "2") (pinfunction "2_2") (pintype "passive"))
      (node (ref "R75") (pin "2") (pinfunction "2_2") (pintype "passive"))
      (node (ref "R76") (pin "2") (pinfunction "2_2") (pintype "passive"))
      (node (ref "R77") (pin "2") (pinfunction "2_2") (pintype "passive"))
      (node (ref "R79") (pin "2") (pinfunction "2_2") (pintype "passive"))
      (node (ref "R80") (pin "2") (pinfunction "2_2") (pintype "passive"))
      (node (ref "S1") (pin "1") (pinfunction "1_1") (pintype "passive"))
      (node (ref "S2") (pin "1") (pinfunction "1_1") (pintype "passive"))
      (node (ref "S3") (pin "1") (pinfunction "1_1") (pintype "passive"))
      (node (ref "U1") (pin "15") (pinfunction "AGND_15") (pintype "power_in"))
      (node (ref "U1") (pin "19") (pinfunction "AGND_19") (pintype "power_in"))
      (node (ref "U1") (pin "35") (pinfunction "IOGND_35") (pintype "power_in"))
      (node (ref "U1") (pin "36") (pinfunction "DGND_36") (pintype "power_in"))
      (node (ref "U1") (pin "47") (pinfunction "IOGND_47") (pintype "power_in"))
      (node (ref "U2") (pin "2") (pinfunction "GND_2") (pintype "power_in"))
      (node (ref "U3") (pin "2") (pinfunction "GND_2") (pintype "power_in"))
      (node (ref "U4") (pin "1") (pinfunction "E0_1") (pintype "input"))
      (node (ref "U4") (pin "2") (pinfunction "E1_2") (pintype "input"))
      (node (ref "U4") (pin "3") (pinfunction "E2_3") (pintype "input"))
      (node (ref "U4") (pin "4") (pinfunction "VSS_4") (pintype "power_in"))
      (node (ref "Y1") (pin "2") (pinfunction "GND_2") (pintype "passive"))
    )
    (net (code "84") (name "Net-(C22-Pad2)") (class "Default")
      (node (ref "C22") (pin "2") (pinfunction "2_2") (pintype "passive"))
      (node (ref "R38") (pin "2") (pinfunction "2_2") (pintype "passive"))
    )
    (net (code "85") (name "Net-(C32-Pad1)") (class "Default")
      (node (ref "C32") (pin "1") (pinfunction "1_1") (pintype "passive"))
      (node (ref "R49") (pin "2") (pinfunction "2_2") (pintype "passive"))
      (node (ref "Y2") (pin "2") (pinfunction "2_2") (pintype "passive"))
    )
    (net (code "86") (name "Net-(C33-Pad1)") (class "Default")
      (node (ref "C33") (pin "1") (pinfunction "1_1") (pintype "passive"))
      (node (ref "J7") (pin "1") (pinfunction "1_1") (pintype "passive"))
      (node (ref "Y2") (pin "1") (pinfunction "1_1") (pintype "passive"))
    )
    (net (code "87") (name "Net-(C34-Pad2)") (class "Default")
      (node (ref "C34") (pin "2") (pinfunction "2_2") (pintype "passive"))
      (node (ref "R57") (pin "2") (pinfunction "2_2") (pintype "passive"))
    )
    (net (code "88") (name "Net-(C35-Pad2)") (class "Default")
      (node (ref "C35") (pin "2") (pinfunction "2_2") (pintype "passive"))
      (node (ref "R59") (pin "2") (pinfunction "2_2") (pintype "passive"))
    )
    (net (code "89") (name "Net-(C42-Pad1)") (class "Default")
      (node (ref "C42") (pin "1") (pinfunction "1_1") (pintype "passive"))
      (node (ref "R73") (pin "2") (pinfunction "2_2") (pintype "passive"))
      (node (ref "Y3") (pin "2") (pinfunction "2_2") (pintype "passive"))
    )
    (net (code "90") (name "Net-(C43-Pad1)") (class "Default")
      (node (ref "C43") (pin "1") (pinfunction "1_1") (pintype "passive"))
      (node (ref "R74") (pin "2") (pinfunction "2_2") (pintype "passive"))
      (node (ref "Y3") (pin "1") (pinfunction "1_1") (pintype "passive"))
    )
    (net (code "91") (name "Net-(D2-K)") (class "Default")
      (node (ref "D2") (pin "2") (pinfunction "K_2") (pintype "passive"))
      (node (ref "R54") (pin "1") (pinfunction "1_1") (pintype "passive"))
      (node (ref "R58") (pin "1") (pinfunction "1_1") (pintype "passive"))
      (node (ref "U2") (pin "3") (pinfunction "FAULT_3") (pintype "output"))
    )
    (net (code "92") (name "Net-(D9-K)") (class "Default")
      (node (ref "D9") (pin "2") (pinfunction "K_2") (pintype "passive"))
      (node (ref "R75") (pin "1") (pinfunction "1_1") (pintype "passive"))
    )
    (net (code "93") (name "Net-(D10-K)") (class "Default")
      (node (ref "D10") (pin "2") (pinfunction "K_2") (pintype "passive"))
      (node (ref "R79") (pin "1") (pinfunction "1_1") (pintype "passive"))
    )
    (net (code "94") (name "Net-(D11-K)") (class "Default")
      (node (ref "D11") (pin "2") (pinfunction "K_2") (pintype "passive"))
      (node (ref "R80") (pin "1") (pinfunction "1_1") (pintype "passive"))
    )
    (net (code "95") (name "Net-(FL1-B)") (class "Default")
      (node (ref "C6") (pin "1") (pinfunction "1_1") (pintype "passive"))
      (node (ref "D1") (pin "2") (pinfunction "2_2") (pintype "passive"))
      (node (ref "FL1") (pin "1") (pinfunction "B_1") (pintype "passive"))
      (node (ref "J1") (pin "1") (pinfunction "1_1") (pintype "power_in"))
    )
    (net (code "96") (name "Net-(FL1-PSG)") (class "Default")
      (node (ref "C6") (pin "2") (pinfunction "2_2") (pintype "passive"))
      (node (ref "D1") (pin "1") (pinfunction "1_1") (pintype "passive"))
      (node (ref "FL1") (pin "3") (pinfunction "PSG_3") (pintype "passive"))
      (node (ref "J1") (pin "2") (pinfunction "2_2") (pintype "power_in"))
      (node (ref "J1") (pin "3") (pinfunction "3_3") (pintype "power_in"))
    )
    (net (code "97") (name "Net-(IC1-ADJ{slash}GND)") (class "Default")
      (node (ref "IC1") (pin "1") (pinfunction "ADJ/GND_1") (pintype "passive"))
      (node (ref "R10") (pin "1") (pinfunction "1_1") (pintype "passive"))
      (node (ref "R14") (pin "2") (pinfunction "2_2") (pintype "passive"))
    )
    (net (code "98") (name "Net-(IC2-D+IN)") (class "Default")
      (node (ref "IC2") (pin "C1") (pinfunction "D+IN_C1") (pintype "passive"))
      (node (ref "J6") (pin "3") (pinfunction "D+_3") (pintype "bidirectional"))
      (node (ref "R28") (pin "1") (pinfunction "1_1") (pintype "passive"))
    )
    (net (code "99") (name "Net-(IC2-D-IN)") (class "Default")
      (node (ref "IC2") (pin "D1") (pinfunction "D-IN_D1") (pintype "passive"))
      (node (ref "J6") (pin "2") (pinfunction "D-_2") (pintype "bidirectional"))
      (node (ref "R37") (pin "1") (pinfunction "1_1") (pintype "passive"))
    )
    (net (code "100") (name "Net-(IC2-ID)") (class "Default")
      (node (ref "IC2") (pin "A3") (pinfunction "ID_A3") (pintype "passive"))
      (node (ref "J6") (pin "4") (pinfunction "ID_4") (pintype "passive"))
      (node (ref "R31") (pin "1") (pinfunction "1_1") (pintype "passive"))
    )
    (net (code "101") (name "Net-(IC3-BYPASS_REG)") (class "Default")
      (node (ref "IC3") (pin "48") (pinfunction "BYPASS_REG_48") (pintype "passive"))
      (node (ref "R77") (pin "1") (pinfunction "1_1") (pintype "passive"))
    )
    (net (code "102") (name "Net-(IC3-PH0)") (class "Default")
      (node (ref "IC3") (pin "29") (pinfunction "PH0_29") (pintype "passive"))
      (node (ref "R73") (pin "1") (pinfunction "1_1") (pintype "passive"))
    )
    (net (code "103") (name "Net-(IC3-PH1)") (class "Default")
      (node (ref "IC3") (pin "30") (pinfunction "PH1_30") (pintype "passive"))
      (node (ref "R74") (pin "1") (pinfunction "1_1") (pintype "passive"))
    )
    (net (code "104") (name "Net-(IC3-VCAP_1)") (class "Default")
      (node (ref "C45") (pin "1") (pinfunction "1_1") (pintype "passive"))
      (node (ref "IC3") (pin "81") (pinfunction "VCAP_1_81") (pintype "passive"))
    )
    (net (code "105") (name "Net-(IC3-VCAP_2)") (class "Default")
      (node (ref "C38") (pin "1") (pinfunction "1_1") (pintype "passive"))
      (node (ref "IC3") (pin "125") (pinfunction "VCAP_2_125") (pintype "passive"))
    )
    (net (code "106") (name "Net-(J2-CD)") (class "Default")
      (node (ref "J2") (pin "10") (pinfunction "CD_10") (pintype "passive"))
      (node (ref "R15") (pin "1") (pinfunction "1_1") (pintype "passive"))
    )
    (net (code "107") (name "Net-(J3-A_GREEN)") (class "Default")
      (node (ref "J3") (pin "9") (pinfunction "A_GREEN_9") (pintype "passive"))
      (node (ref "R11") (pin "2") (pinfunction "2_2") (pintype "passive"))
    )
    (net (code "108") (name "Net-(J3-A_YELLOW)") (class "Default")
      (node (ref "J3") (pin "12") (pinfunction "A_YELLOW_12") (pintype "passive"))
      (node (ref "R13") (pin "2") (pinfunction "2_2") (pintype "passive"))
    )
    (net (code "109") (name "Net-(J4-Pad1)") (class "Default")
      (node (ref "J4") (pin "1") (pinfunction "1_1") (pintype "passive"))
      (node (ref "R19") (pin "2") (pinfunction "2_2") (pintype "passive"))
    )
    (net (code "110") (name "Net-(J4-Pad3)") (class "Default")
      (node (ref "J4") (pin "3") (pinfunction "3_3") (pintype "passive"))
      (node (ref "R22") (pin "1") (pinfunction "1_1") (pintype "passive"))
    )
    (net (code "111") (name "Net-(J5-Pad17)") (class "Default")
      (node (ref "J5") (pin "17") (pinfunction "17_17") (pintype "passive"))
      (node (ref "R51") (pin "2") (pinfunction "2_2") (pintype "passive"))
    )
    (net (code "112") (name "Net-(J5-Pad18)") (class "Default")
      (node (ref "J5") (pin "18") (pinfunction "18_18") (pintype "passive"))
      (node (ref "R52") (pin "1") (pinfunction "1_1") (pintype "passive"))
    )
    (net (code "113") (name "Net-(J7-Pad3)") (class "Default")
      (node (ref "J7") (pin "3") (pinfunction "3_3") (pintype "passive"))
      (node (ref "R56") (pin "2") (pinfunction "2_2") (pintype "passive"))
    )
    (net (code "114") (name "Net-(J8-PadB6)") (class "Default")
      (node (ref "J8") (pin "B6") (pinfunction "B6_B6") (pintype "passive"))
      (node (ref "R67") (pin "1") (pinfunction "1_1") (pintype "passive"))
      (node (ref "R68") (pin "2") (pinfunction "2_2") (pintype "passive"))
    )
    (net (code "115") (name "Net-(J8-PadB9)") (class "Default")
      (node (ref "J8") (pin "B9") (pinfunction "B9_B9") (pintype "passive"))
      (node (ref "R69") (pin "2") (pinfunction "2_2") (pintype "passive"))
    )
    (net (code "116") (name "Net-(J8-PadB10)") (class "Default")
      (node (ref "J8") (pin "B10") (pinfunction "B10_B10") (pintype "passive"))
      (node (ref "R70") (pin "2") (pinfunction "2_2") (pintype "passive"))
    )
    (net (code "117") (name "Net-(U1-CLK_OUT)") (class "Default")
      (node (ref "R19") (pin "1") (pinfunction "1_1") (pintype "passive"))
      (node (ref "U1") (pin "25") (pinfunction "CLK_OUT_25") (pintype "output"))
    )
    (net (code "118") (name "Net-(U1-COL{slash}PHYAD0)") (class "Default")
      (node (ref "R45") (pin "1") (pinfunction "1_1") (pintype "passive"))
      (node (ref "U1") (pin "42") (pinfunction "COL/PHYAD0_42") (pintype "output"))
    )
    (net (code "119") (name "Net-(U1-CRS{slash}CRS_DV{slash}LED_CFG)") (class "Default")
      (node (ref "R44") (pin "1") (pinfunction "1_1") (pintype "passive"))
      (node (ref "U1") (pin "40") (pinfunction "CRS/CRS_DV/LED_CFG_40") (pintype "output"))
    )
    (net (code "120") (name "Net-(U1-LED_SPEED{slash}AN1)") (class "Default")
      (node (ref "R41") (pin "2") (pinfunction "2_2") (pintype "passive"))
      (node (ref "U1") (pin "27") (pinfunction "LED_SPEED/AN1_27") (pintype "output"))
    )
    (net (code "121") (name "Net-(U1-PFBIN1)") (class "Default")
      (node (ref "C25") (pin "1") (pinfunction "1_1") (pintype "passive"))
      (node (ref "C29") (pin "2") (pinfunction "2_2") (pintype "passive"))
      (node (ref "C30") (pin "2") (pinfunction "2_2") (pintype "passive"))
      (node (ref "C31") (pin "2") (pinfunction "2_2") (pintype "passive"))
      (node (ref "U1") (pin "18") (pinfunction "PFBIN1_18") (pintype "input"))
      (node (ref "U1") (pin "23") (pinfunction "PFBOUT_23") (pintype "output"))
      (node (ref "U1") (pin "37") (pinfunction "PFBIN2_37") (pintype "input"))
    )
    (net (code "122") (name "Net-(U1-RBIAS)") (class "Default")
      (node (ref "R43") (pin "2") (pinfunction "2_2") (pintype "passive"))
      (node (ref "U1") (pin "24") (pinfunction "RBIAS_24") (pintype "input"))
    )
    (net (code "123") (name "Net-(U1-RESERVED_20)") (class "Default")
      (node (ref "R47") (pin "2") (pinfunction "2_2") (pintype "passive"))
      (node (ref "U1") (pin "20") (pinfunction "RESERVED_20_20") (pintype "passive"))
    )
    (net (code "124") (name "Net-(U1-RESERVED_31)") (class "Default")
      (node (ref "R48") (pin "2") (pinfunction "2_2") (pintype "passive"))
      (node (ref "U1") (pin "21") (pinfunction "RESERVED_31_21") (pintype "passive"))
    )
    (net (code "125") (name "Net-(U1-RXD_0{slash}PHYAD1)") (class "Default")
      (node (ref "R27") (pin "1") (pinfunction "1_1") (pintype "passive"))
      (node (ref "U1") (pin "43") (pinfunction "RXD_0/PHYAD1_43") (pintype "output"))
    )
    (net (code "126") (name "Net-(U1-RXD_1{slash}PHYAD2)") (class "Default")
      (node (ref "R30") (pin "1") (pinfunction "1_1") (pintype "passive"))
      (node (ref "U1") (pin "44") (pinfunction "RXD_1/PHYAD2_44") (pintype "output"))
    )
    (net (code "127") (name "Net-(U1-RXD_2{slash}PHYAD3)") (class "Default")
      (node (ref "R33") (pin "1") (pinfunction "1_1") (pintype "passive"))
      (node (ref "U1") (pin "45") (pinfunction "RXD_2/PHYAD3_45") (pintype "output"))
    )
    (net (code "128") (name "Net-(U1-RXD_3{slash}PHYAD4)") (class "Default")
      (node (ref "R35") (pin "1") (pinfunction "1_1") (pintype "passive"))
      (node (ref "U1") (pin "46") (pinfunction "RXD_3/PHYAD4_46") (pintype "output"))
    )
    (net (code "129") (name "Net-(U1-RX_CLK)") (class "Default")
      (node (ref "R22") (pin "2") (pinfunction "2_2") (pintype "passive"))
      (node (ref "U1") (pin "38") (pinfunction "RX_CLK_38") (pintype "output"))
    )
    (net (code "130") (name "Net-(U1-RX_DV{slash}MII_MODE)") (class "Default")
      (node (ref "R36") (pin "1") (pinfunction "1_1") (pintype "passive"))
      (node (ref "U1") (pin "39") (pinfunction "RX_DV/MII_MODE_39") (pintype "output"))
    )
    (net (code "131") (name "Net-(U1-RX_ER{slash}MDIX_EN)") (class "Default")
      (node (ref "R39") (pin "1") (pinfunction "1_1") (pintype "passive"))
      (node (ref "U1") (pin "41") (pinfunction "RX_ER/MDIX_EN_41") (pintype "output"))
    )
    (net (code "132") (name "Net-(U1-TXD_0)") (class "Default")
      (node (ref "R24") (pin "2") (pinfunction "2_2") (pintype "passive"))
      (node (ref "U1") (pin "3") (pinfunction "TXD_0_3") (pintype "input"))
    )
    (net (code "133") (name "Net-(U1-TXD_1)") (class "Default")
      (node (ref "R25") (pin "2") (pinfunction "2_2") (pintype "passive"))
      (node (ref "U1") (pin "4") (pinfunction "TXD_1_4") (pintype "input"))
    )
    (net (code "134") (name "Net-(U1-TXD_2)") (class "Default")
      (node (ref "R26") (pin "2") (pinfunction "2_2") (pintype "passive"))
      (node (ref "U1") (pin "5") (pinfunction "TXD_2_5") (pintype "input"))
    )
    (net (code "135") (name "Net-(U1-TXD_3{slash}SNI_MODE)") (class "Default")
      (node (ref "R29") (pin "2") (pinfunction "2_2") (pintype "passive"))
      (node (ref "U1") (pin "6") (pinfunction "TXD_3/SNI_MODE_6") (pintype "input"))
    )
    (net (code "136") (name "Net-(U1-TX_CLK)") (class "Default")
      (node (ref "R34") (pin "2") (pinfunction "2_2") (pintype "passive"))
      (node (ref "U1") (pin "1") (pinfunction "TX_CLK_1") (pintype "output"))
    )
    (net (code "137") (name "Net-(U1-TX_EN)") (class "Default")
      (node (ref "R32") (pin "2") (pinfunction "2_2") (pintype "passive"))
      (node (ref "U1") (pin "2") (pinfunction "TX_EN_2") (pintype "input"))
    )
    (net (code "138") (name "Net-(U2-EN)") (class "Default")
      (node (ref "R53") (pin "1") (pinfunction "1_1") (pintype "passive"))
      (node (ref "R55") (pin "2") (pinfunction "2_2") (pintype "passive"))
      (node (ref "U2") (pin "4") (pinfunction "EN_4") (pintype "input"))
    )
    (net (code "139") (name "Net-(U3-CANH)") (class "Default")
      (node (ref "J9") (pin "7") (pinfunction "7_7") (pintype "passive"))
      (node (ref "U3") (pin "7") (pinfunction "CANH_7") (pintype "output"))
    )
    (net (code "140") (name "Net-(U3-CANL)") (class "Default")
      (node (ref "J9") (pin "3") (pinfunction "3_3") (pintype "passive"))
      (node (ref "U3") (pin "6") (pinfunction "CANL_6") (pintype "output"))
    )
    (net (code "141") (name "Net-(U3-RS)") (class "Default")
      (node (ref "R76") (pin "1") (pinfunction "1_1") (pintype "passive"))
      (node (ref "U3") (pin "8") (pinfunction "RS_8") (pintype "input"))
    )
    (net (code "142") (name "Net-(U4-~{WC})") (class "Default")
      (node (ref "R78") (pin "2") (pinfunction "2_2") (pintype "passive"))
      (node (ref "U4") (pin "7") (pinfunction "~{WC}_7") (pintype "input"))
    )
    (net (code "143") (name "Net-(Y1-STANDBY)") (class "Default")
      (node (ref "R46") (pin "1") (pinfunction "1_1") (pintype "passive"))
      (node (ref "Y1") (pin "1") (pinfunction "STANDBY_1") (pintype "passive"))
    )
    (net (code "144") (name "VBUS_USB") (class "Default")
      (node (ref "IC2") (pin "B3") (pinfunction "VBUS_B3") (pintype "passive"))
      (node (ref "IC3") (pin "120") (pinfunction "PA9_120") (pintype "passive"))
      (node (ref "J6") (pin "1") (pinfunction "VBUS_1") (pintype "passive"))
      (node (ref "U2") (pin "1") (pinfunction "OUT_1") (pintype "output"))
    )
    (net (code "145") (name "VDD_MCU") (class "Default")
      (node (ref "C10") (pin "2") (pinfunction "2_2") (pintype "passive"))
      (node (ref "C11") (pin "2") (pinfunction "2_2") (pintype "passive"))
      (node (ref "C12") (pin "2") (pinfunction "2_2") (pintype "passive"))
      (node (ref "C13") (pin "2") (pinfunction "2_2") (pintype "passive"))
      (node (ref "C14") (pin "2") (pinfunction "2_2") (pintype "passive"))
      (node (ref "C15") (pin "2") (pinfunction "2_2") (pintype "passive"))
      (node (ref "C16") (pin "2") (pinfunction "2_2") (pintype "passive"))
      (node (ref "C17") (pin "2") (pinfunction "2_2") (pintype "passive"))
      (node (ref "C18") (pin "2") (pinfunction "2_2") (pintype "passive"))
      (node (ref "C19") (pin "2") (pinfunction "2_2") (pintype "passive"))
      (node (ref "C20") (pin "2") (pinfunction "2_2") (pintype "passive"))
      (node (ref "C21") (pin "2") (pinfunction "2_2") (pintype "passive"))
      (node (ref "C8") (pin "2") (pinfunction "2_2") (pintype "passive"))
      (node (ref "C9") (pin "2") (pinfunction "2_2") (pintype "passive"))
      (node (ref "FL2") (pin "1") (pinfunction "1_1") (pintype "passive"))
      (node (ref "IC3") (pin "103") (pinfunction "VDD_9_103") (pintype "power_in"))
      (node (ref "IC3") (pin "114") (pinfunction "VDD_10_114") (pintype "power_in"))
      (node (ref "IC3") (pin "127") (pinfunction "VDD_11_127") (pintype "power_in"))
      (node (ref "IC3") (pin "136") (pinfunction "VDD_12_136") (pintype "power_in"))
      (node (ref "IC3") (pin "149") (pinfunction "VDD_13_149") (pintype "power_in"))
      (node (ref "IC3") (pin "15") (pinfunction "VDD_1_15") (pintype "power_in"))
      (node (ref "IC3") (pin "159") (pinfunction "VDD_14_159") (pintype "power_in"))
      (node (ref "IC3") (pin "172") (pinfunction "VDD_15_172") (pintype "power_in"))
      (node (ref "IC3") (pin "23") (pinfunction "VDD_2_23") (pintype "power_in"))
      (node (ref "IC3") (pin "36") (pinfunction "VDD_3_36") (pintype "power_in"))
      (node (ref "IC3") (pin "49") (pinfunction "VDD_4_49") (pintype "power_in"))
      (node (ref "IC3") (pin "62") (pinfunction "VDD_5_62") (pintype "power_in"))
      (node (ref "IC3") (pin "72") (pinfunction "VDD_6_72") (pintype "power_in"))
      (node (ref "IC3") (pin "82") (pinfunction "VDD_7_82") (pintype "power_in"))
      (node (ref "IC3") (pin "91") (pinfunction "VDD_8_91") (pintype "power_in"))
      (node (ref "R16") (pin "2") (pinfunction "2_2") (pintype "passive"))
    )
    (net (code "146") (name "unconnected-(IC2-DZ-PadA2)") (class "Default")
      (node (ref "IC2") (pin "A2") (pinfunction "DZ_A2") (pintype "passive"))
    )
    (net (code "147") (name "unconnected-(IC2-GND-PadD2)") (class "Default")
      (node (ref "IC2") (pin "D2") (pinfunction "GND_D2") (pintype "passive"))
    )
    (net (code "148") (name "unconnected-(IC2-PD1-PadB1)") (class "Default")
      (node (ref "IC2") (pin "B1") (pinfunction "PD1_B1") (pintype "passive"))
    )
    (net (code "149") (name "unconnected-(IC2-PD2-PadC2)") (class "Default")
      (node (ref "IC2") (pin "C2") (pinfunction "PD2_C2") (pintype "passive"))
    )
    (net (code "150") (name "unconnected-(IC2-PUP-PadB2)") (class "Default")
      (node (ref "IC2") (pin "B2") (pinfunction "PUP_B2") (pintype "passive"))
    )
    (net (code "151") (name "unconnected-(IC3-PA3-Pad47)") (class "Default")
      (node (ref "IC3") (pin "47") (pinfunction "PA3_47") (pintype "passive+no_connect"))
    )
    (net (code "152") (name "unconnected-(IC3-PA4-Pad50)") (class "Default")
      (node (ref "IC3") (pin "50") (pinfunction "PA4_50") (pintype "passive+no_connect"))
    )
    (net (code "153") (name "unconnected-(IC3-PA5-Pad51)") (class "Default")
      (node (ref "IC3") (pin "51") (pinfunction "PA5_51") (pintype "passive+no_connect"))
    )
    (net (code "154") (name "unconnected-(IC3-PB0-Pad56)") (class "Default")
      (node (ref "IC3") (pin "56") (pinfunction "PB0_56") (pintype "passive+no_connect"))
    )
    (net (code "155") (name "unconnected-(IC3-PB1-Pad57)") (class "Default")
      (node (ref "IC3") (pin "57") (pinfunction "PB1_57") (pintype "passive+no_connect"))
    )
    (net (code "156") (name "unconnected-(IC3-PB7-Pad165)") (class "Default")
      (node (ref "IC3") (pin "165") (pinfunction "PB7_165") (pintype "passive+no_connect"))
    )
    (net (code "157") (name "unconnected-(IC3-PB10-Pad79)") (class "Default")
      (node (ref "IC3") (pin "79") (pinfunction "PB10_79") (pintype "passive+no_connect"))
    )
    (net (code "158") (name "unconnected-(IC3-PB11-Pad80)") (class "Default")
      (node (ref "IC3") (pin "80") (pinfunction "PB11_80") (pintype "passive+no_connect"))
    )
    (net (code "159") (name "unconnected-(IC3-PB12-Pad92)") (class "Default")
      (node (ref "IC3") (pin "92") (pinfunction "PB12_92") (pintype "passive+no_connect"))
    )
    (net (code "160") (name "unconnected-(IC3-PB15-Pad95)") (class "Default")
      (node (ref "IC3") (pin "95") (pinfunction "PB15_95") (pintype "passive+no_connect"))
    )
    (net (code "161") (name "unconnected-(IC3-PC0-Pad32)") (class "Default")
      (node (ref "IC3") (pin "32") (pinfunction "PC0_32") (pintype "passive+no_connect"))
    )
    (net (code "162") (name "unconnected-(IC3-PC6-Pad115)") (class "Default")
      (node (ref "IC3") (pin "115") (pinfunction "PC6_115") (pintype "passive+no_connect"))
    )
    (net (code "163") (name "unconnected-(IC3-PC14-Pad9)") (class "Default")
      (node (ref "IC3") (pin "9") (pinfunction "PC14_9") (pintype "passive+no_connect"))
    )
    (net (code "164") (name "unconnected-(IC3-PC15-Pad10)") (class "Default")
      (node (ref "IC3") (pin "10") (pinfunction "PC15_10") (pintype "passive+no_connect"))
    )
    (net (code "165") (name "unconnected-(IC3-PD0-Pad142)") (class "Default")
      (node (ref "IC3") (pin "142") (pinfunction "PD0_142") (pintype "passive+no_connect"))
    )
    (net (code "166") (name "unconnected-(IC3-PD1-Pad143)") (class "Default")
      (node (ref "IC3") (pin "143") (pinfunction "PD1_143") (pintype "passive+no_connect"))
    )
    (net (code "167") (name "unconnected-(IC3-PD3-Pad145)") (class "Default")
      (node (ref "IC3") (pin "145") (pinfunction "PD3_145") (pintype "passive+no_connect"))
    )
    (net (code "168") (name "unconnected-(IC3-PD4-Pad146)") (class "Default")
      (node (ref "IC3") (pin "146") (pinfunction "PD4_146") (pintype "passive+no_connect"))
    )
    (net (code "169") (name "unconnected-(IC3-PD5-Pad147)") (class "Default")
      (node (ref "IC3") (pin "147") (pinfunction "PD5_147") (pintype "passive+no_connect"))
    )
    (net (code "170") (name "unconnected-(IC3-PD6-Pad150)") (class "Default")
      (node (ref "IC3") (pin "150") (pinfunction "PD6_150") (pintype "passive+no_connect"))
    )
    (net (code "171") (name "unconnected-(IC3-PD7-Pad151)") (class "Default")
      (node (ref "IC3") (pin "151") (pinfunction "PD7_151") (pintype "passive+no_connect"))
    )
    (net (code "172") (name "unconnected-(IC3-PD8-Pad96)") (class "Default")
      (node (ref "IC3") (pin "96") (pinfunction "PD8_96") (pintype "passive+no_connect"))
    )
    (net (code "173") (name "unconnected-(IC3-PD9-Pad97)") (class "Default")
      (node (ref "IC3") (pin "97") (pinfunction "PD9_97") (pintype "passive+no_connect"))
    )
    (net (code "174") (name "unconnected-(IC3-PD10-Pad98)") (class "Default")
      (node (ref "IC3") (pin "98") (pinfunction "PD10_98") (pintype "passive+no_connect"))
    )
    (net (code "175") (name "unconnected-(IC3-PD11-Pad99)") (class "Default")
      (node (ref "IC3") (pin "99") (pinfunction "PD11_99") (pintype "passive+no_connect"))
    )
    (net (code "176") (name "unconnected-(IC3-PD12-Pad100)") (class "Default")
      (node (ref "IC3") (pin "100") (pinfunction "PD12_100") (pintype "passive+no_connect"))
    )
    (net (code "177") (name "unconnected-(IC3-PD13-Pad101)") (class "Default")
      (node (ref "IC3") (pin "101") (pinfunction "PD13_101") (pintype "passive+no_connect"))
    )
    (net (code "178") (name "unconnected-(IC3-PD14-Pad104)") (class "Default")
      (node (ref "IC3") (pin "104") (pinfunction "PD14_104") (pintype "passive+no_connect"))
    )
    (net (code "179") (name "unconnected-(IC3-PD15-Pad105)") (class "Default")
      (node (ref "IC3") (pin "105") (pinfunction "PD15_105") (pintype "passive+no_connect"))
    )
    (net (code "180") (name "unconnected-(IC3-PDR_ON-Pad171)") (class "Default")
      (node (ref "IC3") (pin "171") (pinfunction "PDR_ON_171") (pintype "passive+no_connect"))
    )
    (net (code "181") (name "unconnected-(IC3-PE0-Pad169)") (class "Default")
      (node (ref "IC3") (pin "169") (pinfunction "PE0_169") (pintype "passive+no_connect"))
    )
    (net (code "182") (name "unconnected-(IC3-PE1-Pad170)") (class "Default")
      (node (ref "IC3") (pin "170") (pinfunction "PE1_170") (pintype "passive+no_connect"))
    )
    (net (code "183") (name "unconnected-(IC3-PE2-Pad1)") (class "Default")
      (node (ref "IC3") (pin "1") (pinfunction "PE2_1") (pintype "passive+no_connect"))
    )
    (net (code "184") (name "unconnected-(IC3-PE3-Pad2)") (class "Default")
      (node (ref "IC3") (pin "2") (pinfunction "PE3_2") (pintype "passive+no_connect"))
    )
    (net (code "185") (name "unconnected-(IC3-PE4-Pad3)") (class "Default")
      (node (ref "IC3") (pin "3") (pinfunction "PE4_3") (pintype "passive+no_connect"))
    )
    (net (code "186") (name "unconnected-(IC3-PE5-Pad4)") (class "Default")
      (node (ref "IC3") (pin "4") (pinfunction "PE5_4") (pintype "passive+no_connect"))
    )
    (net (code "187") (name "unconnected-(IC3-PE6-Pad5)") (class "Default")
      (node (ref "IC3") (pin "5") (pinfunction "PE6_5") (pintype "passive+no_connect"))
    )
    (net (code "188") (name "unconnected-(IC3-PE7-Pad68)") (class "Default")
      (node (ref "IC3") (pin "68") (pinfunction "PE7_68") (pintype "passive+no_connect"))
    )
    (net (code "189") (name "unconnected-(IC3-PE8-Pad69)") (class "Default")
      (node (ref "IC3") (pin "69") (pinfunction "PE8_69") (pintype "passive+no_connect"))
    )
    (net (code "190") (name "unconnected-(IC3-PE9-Pad70)") (class "Default")
      (node (ref "IC3") (pin "70") (pinfunction "PE9_70") (pintype "passive+no_connect"))
    )
    (net (code "191") (name "unconnected-(IC3-PE10-Pad73)") (class "Default")
      (node (ref "IC3") (pin "73") (pinfunction "PE10_73") (pintype "passive+no_connect"))
    )
    (net (code "192") (name "unconnected-(IC3-PE11-Pad74)") (class "Default")
      (node (ref "IC3") (pin "74") (pinfunction "PE11_74") (pintype "passive+no_connect"))
    )
    (net (code "193") (name "unconnected-(IC3-PE12-Pad75)") (class "Default")
      (node (ref "IC3") (pin "75") (pinfunction "PE12_75") (pintype "passive+no_connect"))
    )
    (net (code "194") (name "unconnected-(IC3-PE13-Pad76)") (class "Default")
      (node (ref "IC3") (pin "76") (pinfunction "PE13_76") (pintype "passive+no_connect"))
    )
    (net (code "195") (name "unconnected-(IC3-PE14-Pad77)") (class "Default")
      (node (ref "IC3") (pin "77") (pinfunction "PE14_77") (pintype "passive+no_connect"))
    )
    (net (code "196") (name "unconnected-(IC3-PE15-Pad78)") (class "Default")
      (node (ref "IC3") (pin "78") (pinfunction "PE15_78") (pintype "passive+no_connect"))
    )
    (net (code "197") (name "unconnected-(IC3-PF2-Pad18)") (class "Default")
      (node (ref "IC3") (pin "18") (pinfunction "PF2_18") (pintype "passive+no_connect"))
    )
    (net (code "198") (name "unconnected-(IC3-PF3-Pad19)") (class "Default")
      (node (ref "IC3") (pin "19") (pinfunction "PF3_19") (pintype "passive+no_connect"))
    )
    (net (code "199") (name "unconnected-(IC3-PF4-Pad20)") (class "Default")
      (node (ref "IC3") (pin "20") (pinfunction "PF4_20") (pintype "passive+no_connect"))
    )
    (net (code "200") (name "unconnected-(IC3-PF5-Pad21)") (class "Default")
      (node (ref "IC3") (pin "21") (pinfunction "PF5_21") (pintype "passive+no_connect"))
    )
    (net (code "201") (name "unconnected-(IC3-PF6-Pad24)") (class "Default")
      (node (ref "IC3") (pin "24") (pinfunction "PF6_24") (pintype "passive+no_connect"))
    )
    (net (code "202") (name "unconnected-(IC3-PF7-Pad25)") (class "Default")
      (node (ref "IC3") (pin "25") (pinfunction "PF7_25") (pintype "passive+no_connect"))
    )
    (net (code "203") (name "unconnected-(IC3-PF8-Pad26)") (class "Default")
      (node (ref "IC3") (pin "26") (pinfunction "PF8_26") (pintype "passive+no_connect"))
    )
    (net (code "204") (name "unconnected-(IC3-PF9-Pad27)") (class "Default")
      (node (ref "IC3") (pin "27") (pinfunction "PF9_27") (pintype "passive+no_connect"))
    )
    (net (code "205") (name "unconnected-(IC3-PF10-Pad28)") (class "Default")
      (node (ref "IC3") (pin "28") (pinfunction "PF10_28") (pintype "passive+no_connect"))
    )
    (net (code "206") (name "unconnected-(IC3-PF12-Pad60)") (class "Default")
      (node (ref "IC3") (pin "60") (pinfunction "PF12_60") (pintype "passive+no_connect"))
    )
    (net (code "207") (name "unconnected-(IC3-PF13-Pad63)") (class "Default")
      (node (ref "IC3") (pin "63") (pinfunction "PF13_63") (pintype "passive+no_connect"))
    )
    (net (code "208") (name "unconnected-(IC3-PF14-Pad64)") (class "Default")
      (node (ref "IC3") (pin "64") (pinfunction "PF14_64") (pintype "passive+no_connect"))
    )
    (net (code "209") (name "unconnected-(IC3-PF15-Pad65)") (class "Default")
      (node (ref "IC3") (pin "65") (pinfunction "PF15_65") (pintype "passive+no_connect"))
    )
    (net (code "210") (name "unconnected-(IC3-PG0-Pad66)") (class "Default")
      (node (ref "IC3") (pin "66") (pinfunction "PG0_66") (pintype "passive+no_connect"))
    )
    (net (code "211") (name "unconnected-(IC3-PG1-Pad67)") (class "Default")
      (node (ref "IC3") (pin "67") (pinfunction "PG1_67") (pintype "passive+no_connect"))
    )
    (net (code "212") (name "unconnected-(IC3-PG2-Pad106)") (class "Default")
      (node (ref "IC3") (pin "106") (pinfunction "PG2_106") (pintype "passive+no_connect"))
    )
    (net (code "213") (name "unconnected-(IC3-PG3-Pad107)") (class "Default")
      (node (ref "IC3") (pin "107") (pinfunction "PG3_107") (pintype "passive+no_connect"))
    )
    (net (code "214") (name "unconnected-(IC3-PG4-Pad108)") (class "Default")
      (node (ref "IC3") (pin "108") (pinfunction "PG4_108") (pintype "passive+no_connect"))
    )
    (net (code "215") (name "unconnected-(IC3-PG5-Pad109)") (class "Default")
      (node (ref "IC3") (pin "109") (pinfunction "PG5_109") (pintype "passive+no_connect"))
    )
    (net (code "216") (name "unconnected-(IC3-PG7-Pad111)") (class "Default")
      (node (ref "IC3") (pin "111") (pinfunction "PG7_111") (pintype "passive+no_connect"))
    )
    (net (code "217") (name "unconnected-(IC3-PG9-Pad152)") (class "Default")
      (node (ref "IC3") (pin "152") (pinfunction "PG9_152") (pintype "passive+no_connect"))
    )
    (net (code "218") (name "unconnected-(IC3-PG10-Pad153)") (class "Default")
      (node (ref "IC3") (pin "153") (pinfunction "PG10_153") (pintype "passive+no_connect"))
    )
    (net (code "219") (name "unconnected-(IC3-PG12-Pad155)") (class "Default")
      (node (ref "IC3") (pin "155") (pinfunction "PG12_155") (pintype "passive+no_connect"))
    )
    (net (code "220") (name "unconnected-(IC3-PH4-Pad45)") (class "Default")
      (node (ref "IC3") (pin "45") (pinfunction "PH4_45") (pintype "passive+no_connect"))
    )
    (net (code "221") (name "unconnected-(IC3-PH15-Pad130)") (class "Default")
      (node (ref "IC3") (pin "130") (pinfunction "PH15_130") (pintype "passive+no_connect"))
    )
    (net (code "222") (name "unconnected-(IC3-PI0-Pad131)") (class "Default")
      (node (ref "IC3") (pin "131") (pinfunction "PI0_131") (pintype "passive+no_connect"))
    )
    (net (code "223") (name "unconnected-(IC3-PI1-Pad132)") (class "Default")
      (node (ref "IC3") (pin "132") (pinfunction "PI1_132") (pintype "passive+no_connect"))
    )
    (net (code "224") (name "unconnected-(IC3-PI2-Pad133)") (class "Default")
      (node (ref "IC3") (pin "133") (pinfunction "PI2_133") (pintype "passive+no_connect"))
    )
    (net (code "225") (name "unconnected-(IC3-PI3-Pad134)") (class "Default")
      (node (ref "IC3") (pin "134") (pinfunction "PI3_134") (pintype "passive+no_connect"))
    )
    (net (code "226") (name "unconnected-(IC3-PI8-Pad7)") (class "Default")
      (node (ref "IC3") (pin "7") (pinfunction "PI8_7") (pintype "passive+no_connect"))
    )
    (net (code "227") (name "unconnected-(IC3-PI11-Pad13)") (class "Default")
      (node (ref "IC3") (pin "13") (pinfunction "PI11_13") (pintype "passive+no_connect"))
    )
    (net (code "228") (name "unconnected-(J3-NC-Pad7)") (class "Default")
      (node (ref "J3") (pin "7") (pinfunction "NC_7") (pintype "passive+no_connect"))
    )
    (net (code "229") (name "unconnected-(J9-Pad1)") (class "Default")
      (node (ref "J9") (pin "1") (pinfunction "1_1") (pintype "passive+no_connect"))
    )
    (net (code "230") (name "unconnected-(J9-Pad6)") (class "Default")
      (node (ref "J9") (pin "6") (pinfunction "6_6") (pintype "passive+no_connect"))
    )
    (net (code "231") (name "unconnected-(U1-TCK-Pad8)") (class "Default")
      (node (ref "U1") (pin "8") (pinfunction "TCK_8") (pintype "input+no_connect"))
    )
    (net (code "232") (name "unconnected-(U1-TDI-Pad12)") (class "Default")
      (node (ref "U1") (pin "12") (pinfunction "TDI_12") (pintype "input+no_connect"))
    )
    (net (code "233") (name "unconnected-(U1-TDO-Pad9)") (class "Default")
      (node (ref "U1") (pin "9") (pinfunction "TDO_9") (pintype "output+no_connect"))
    )
    (net (code "234") (name "unconnected-(U1-TMS-Pad10)") (class "Default")
      (node (ref "U1") (pin "10") (pinfunction "TMS_10") (pintype "input+no_connect"))
    )
    (net (code "235") (name "unconnected-(U1-~{TRST}-Pad11)") (class "Default")
      (node (ref "U1") (pin "11") (pinfunction "~{TRST}_11") (pintype "input+no_connect"))
    )
    (net (code "236") (name "unconnected-(U3-VREF-Pad5)") (class "Default")
      (node (ref "U3") (pin "5") (pinfunction "VREF_5") (pintype "output"))
    )
  )
)
